# On_Axis_Encoder.net
KiCad netlist of a schematic drawn in EAGLE
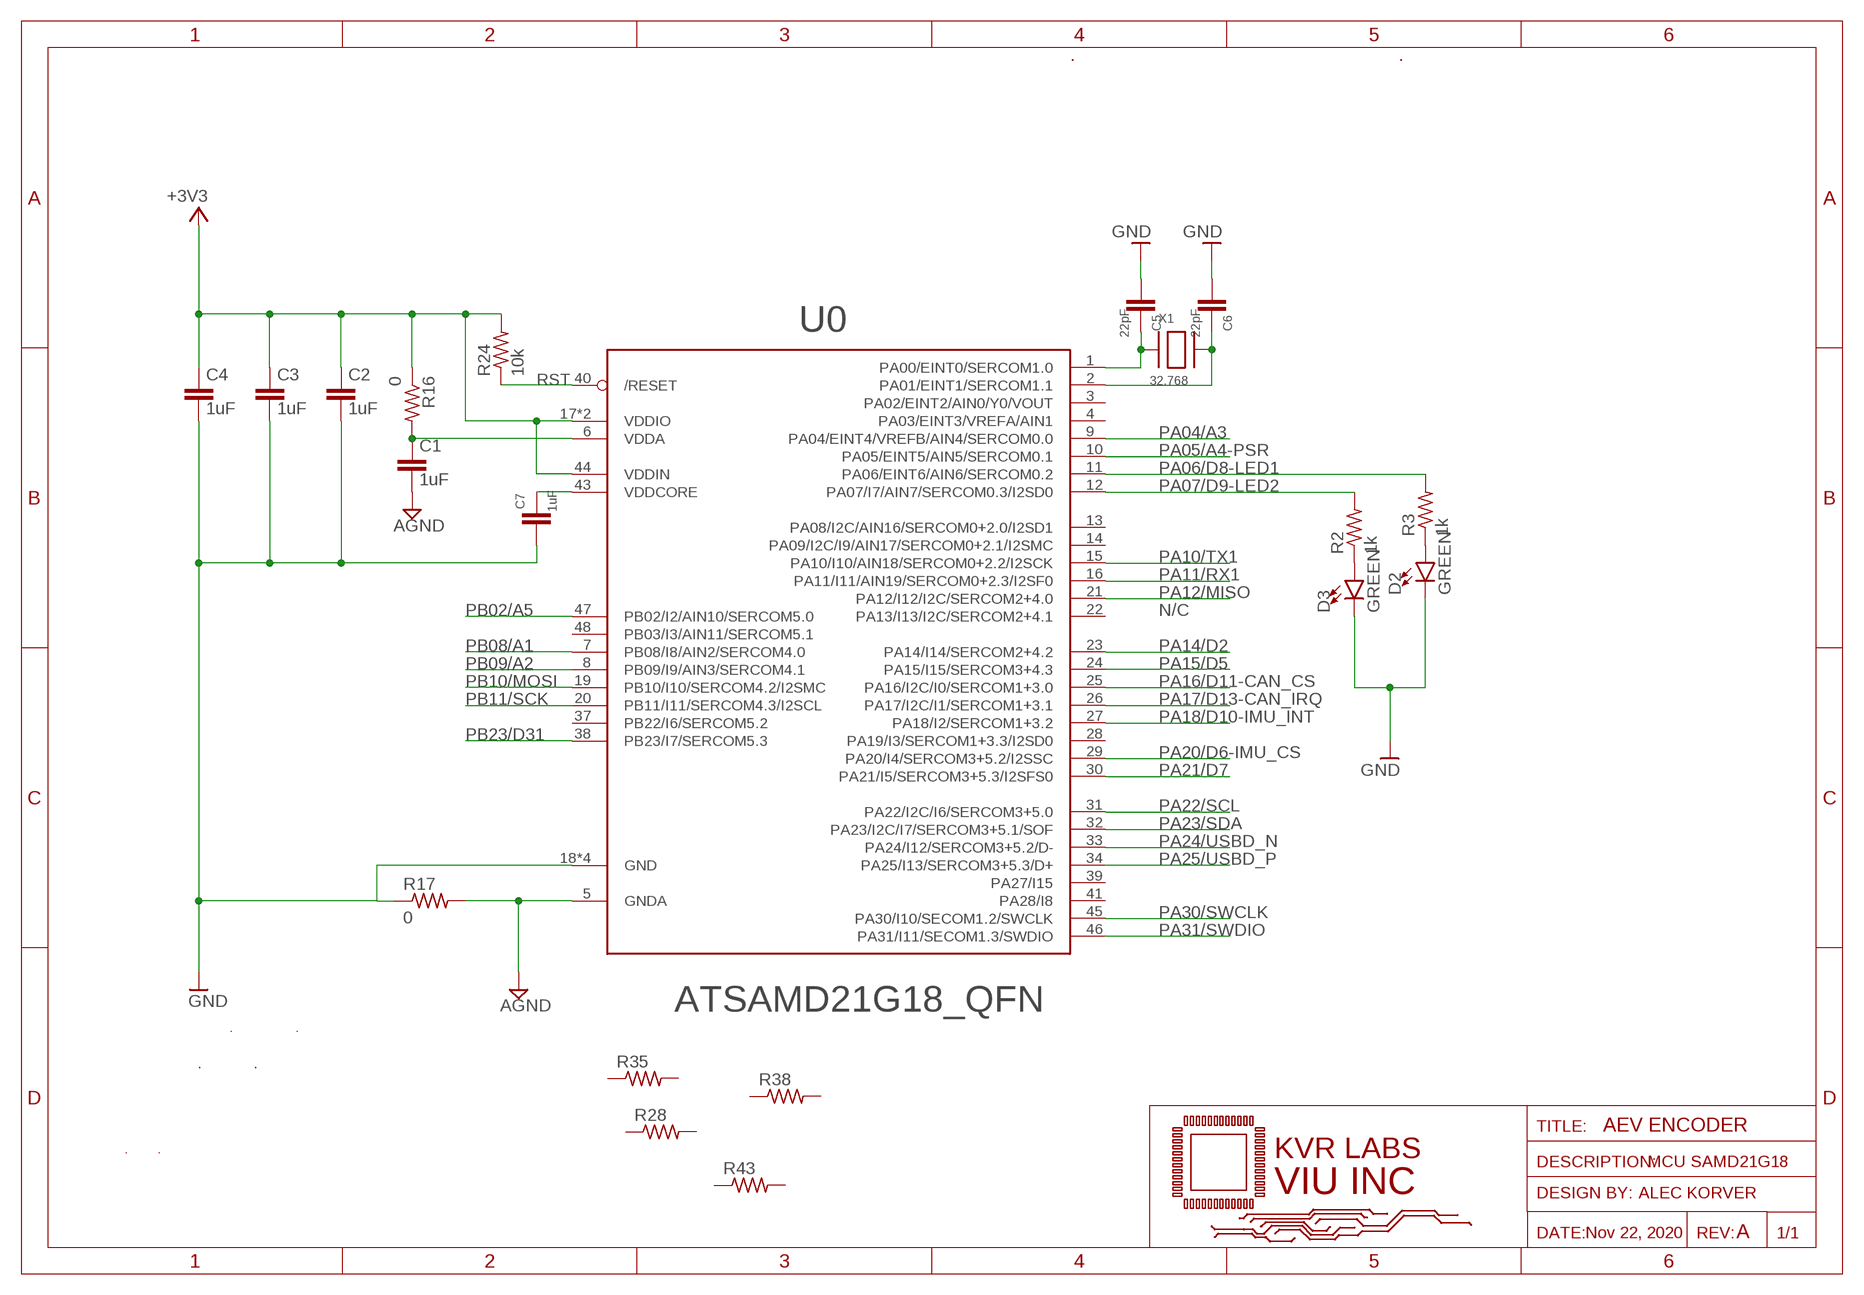
[diagram p0: schematic, sheet 1]
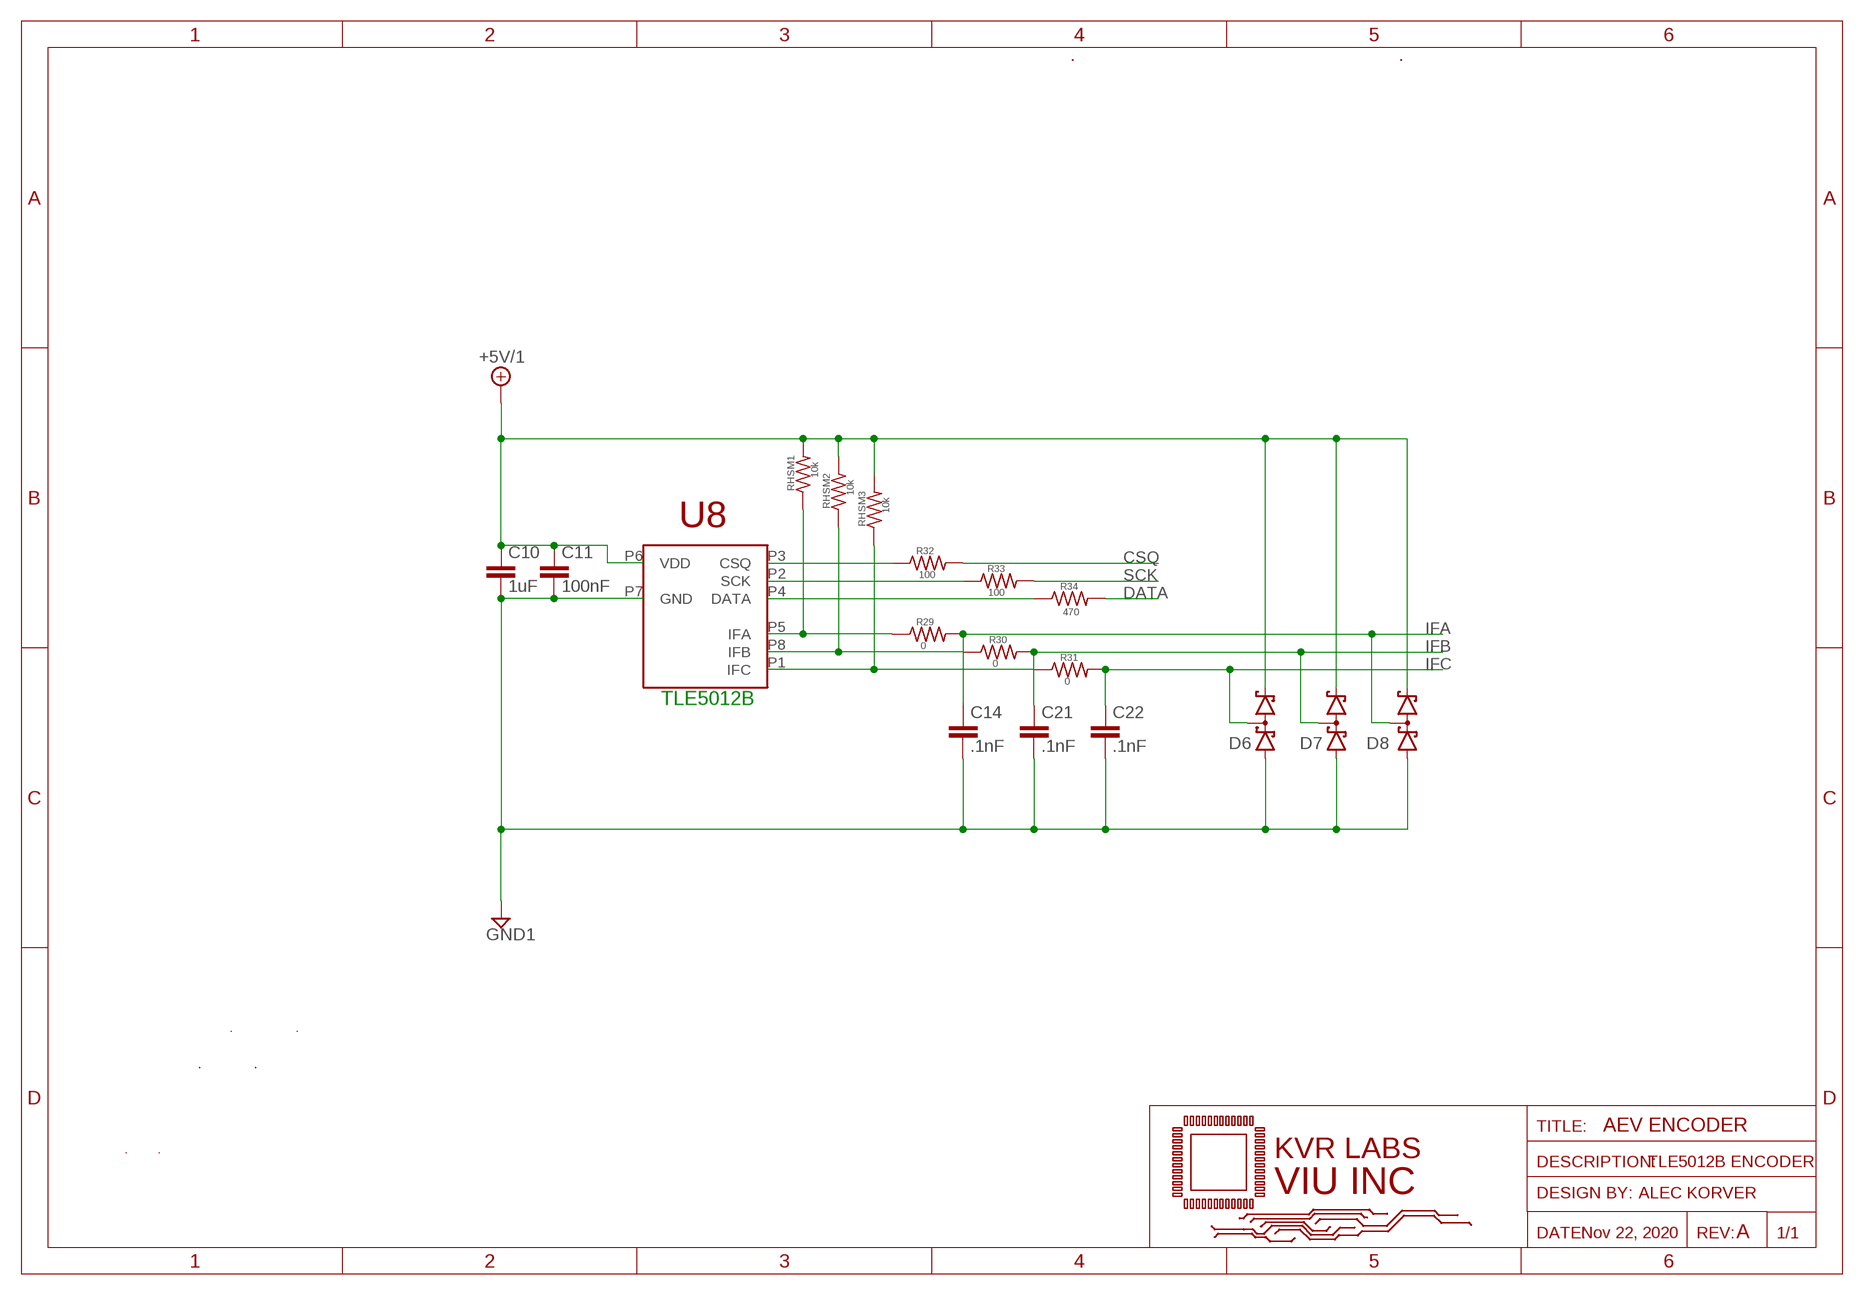
[diagram p1: schematic, sheet 2]
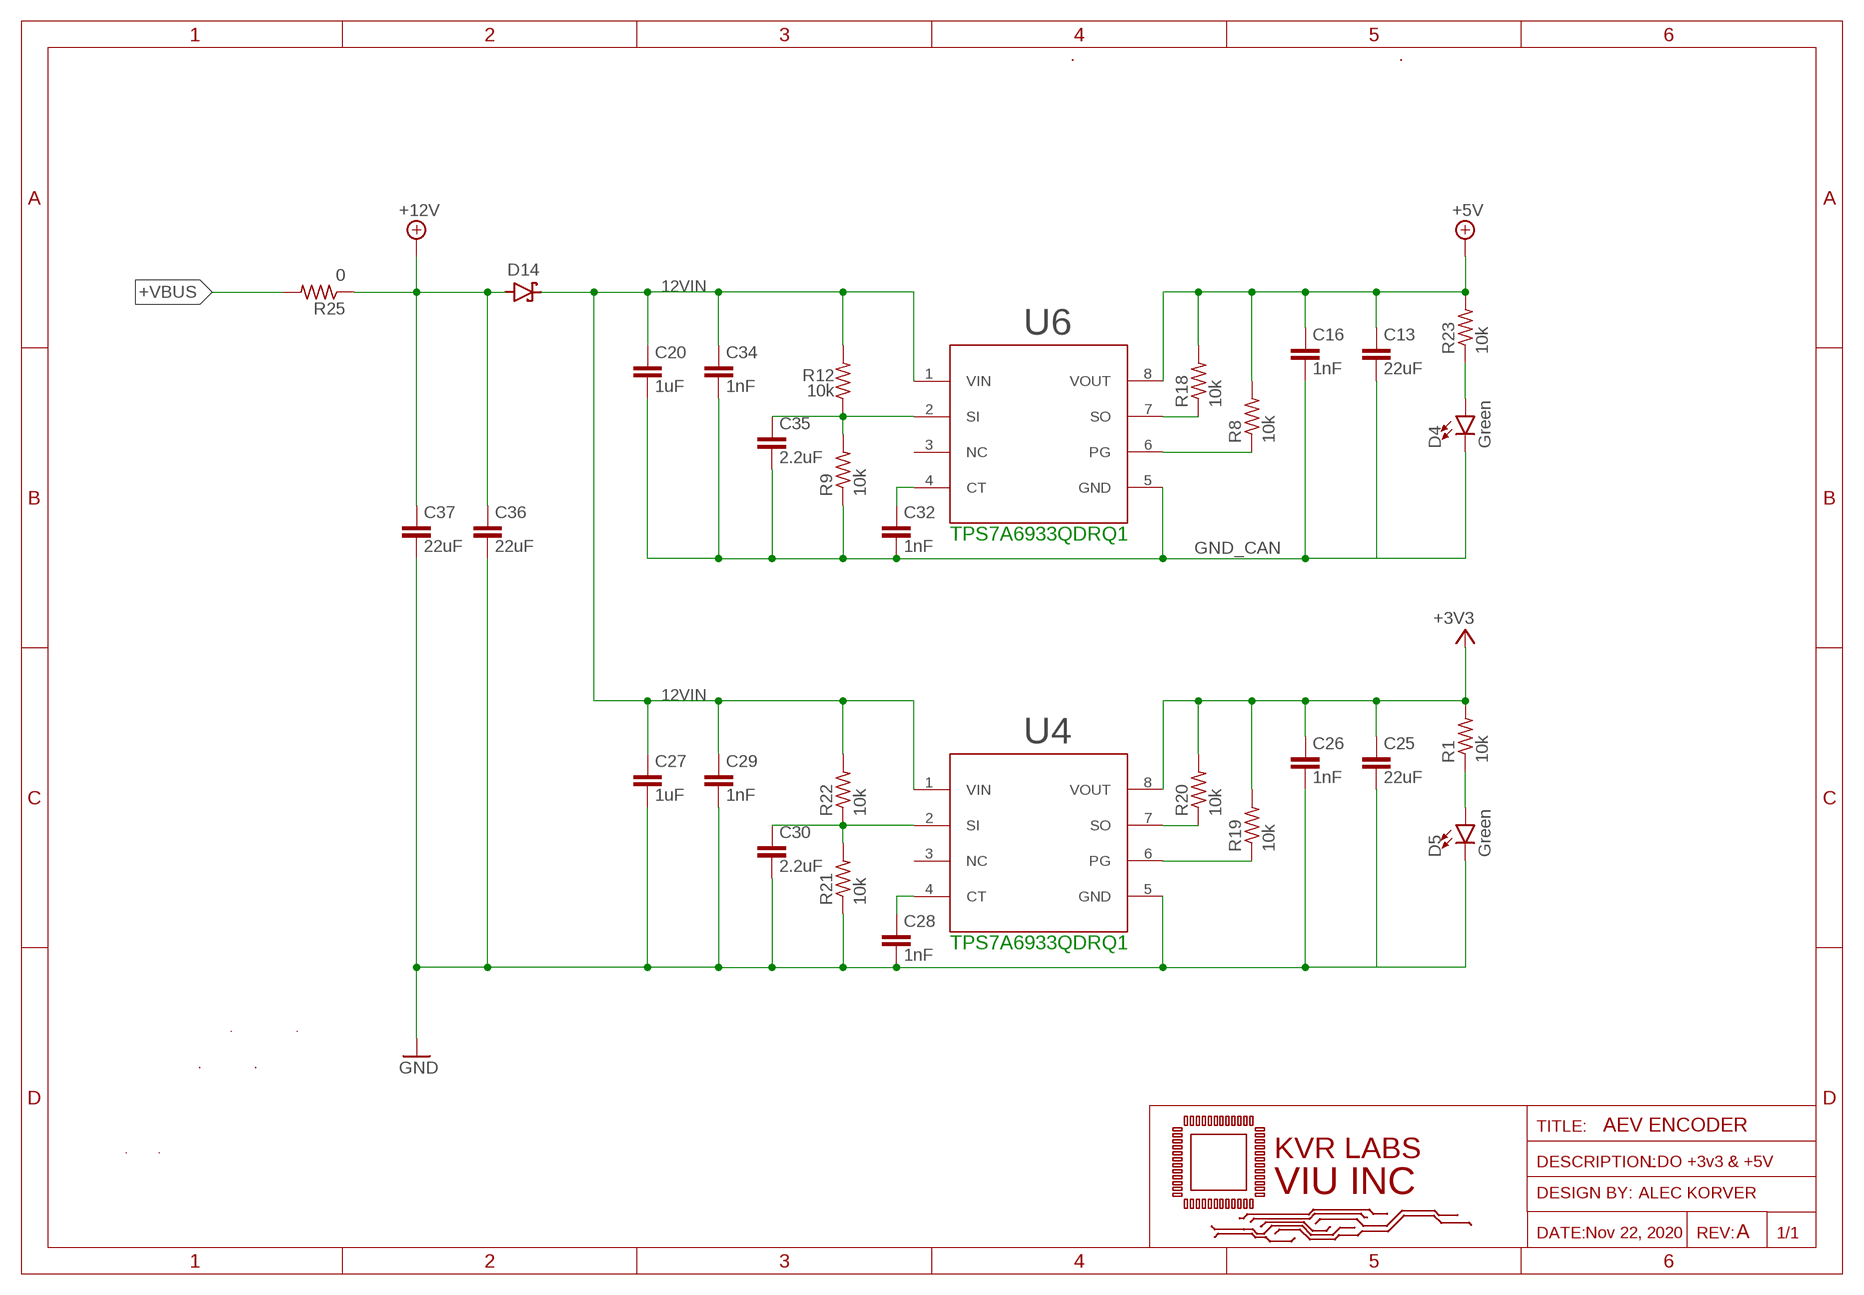
[diagram p2: schematic, sheet 3]
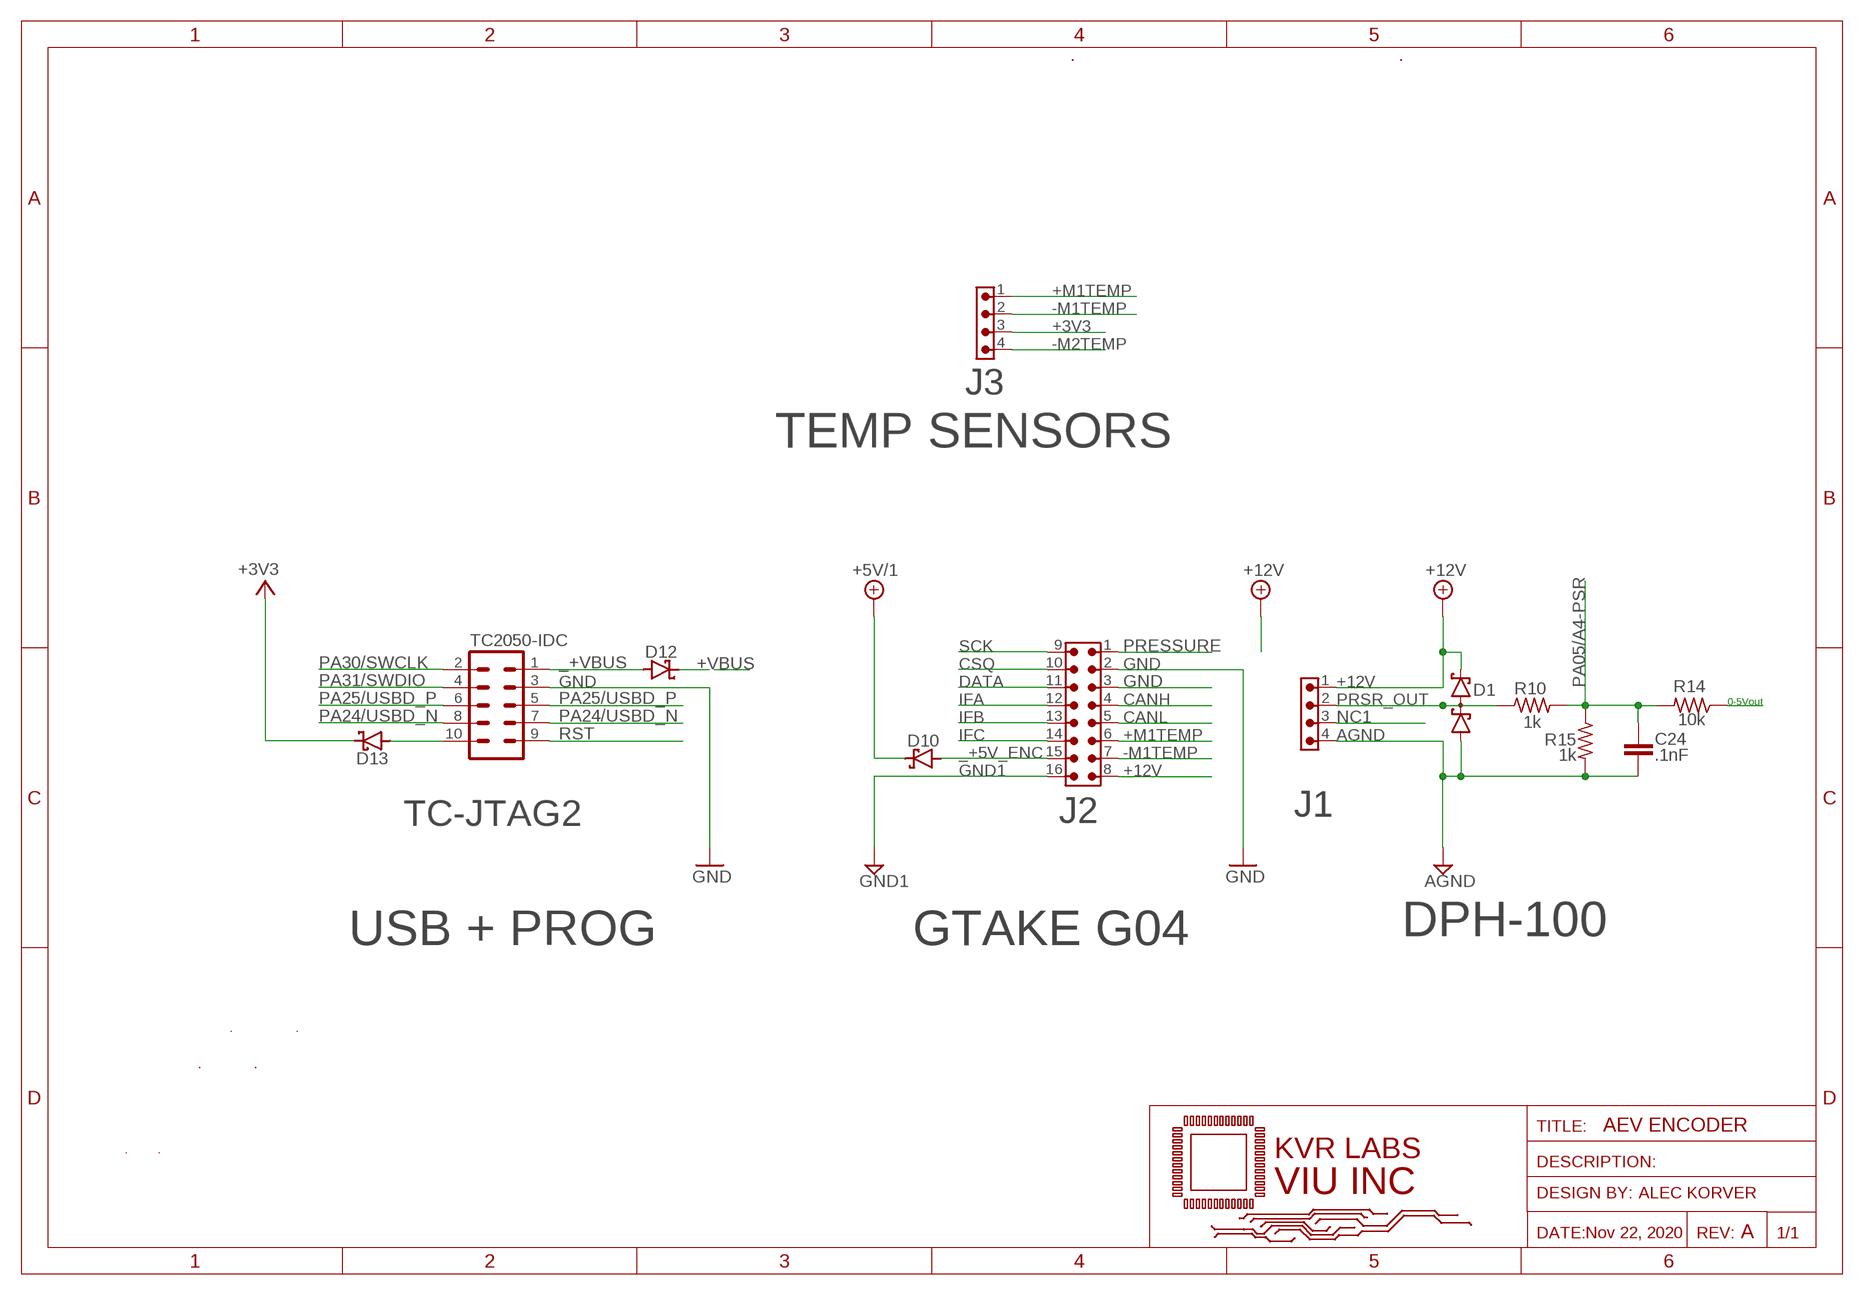
[diagram p3: schematic, sheet 4]
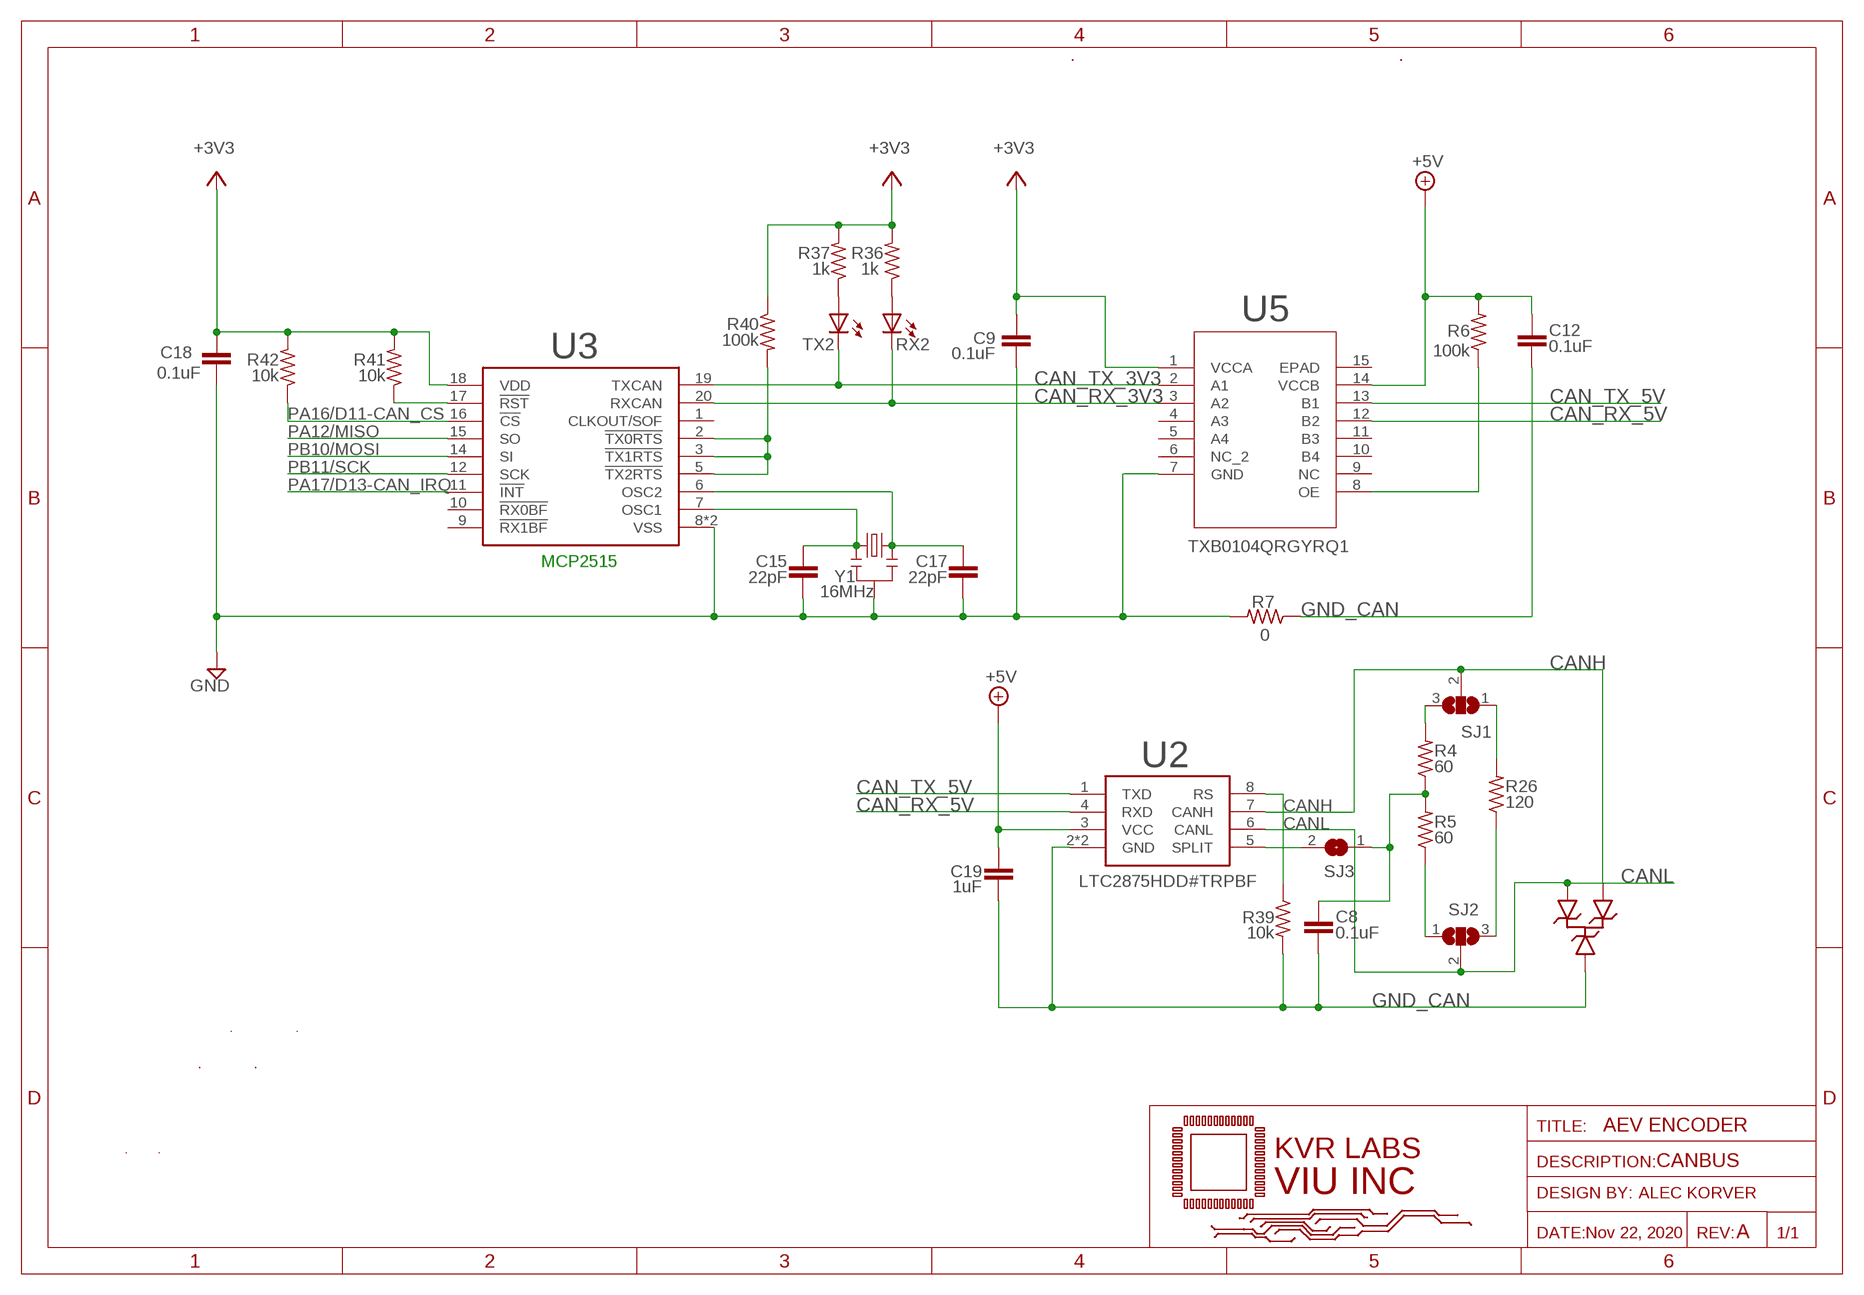
[diagram p4: schematic, sheet 5]
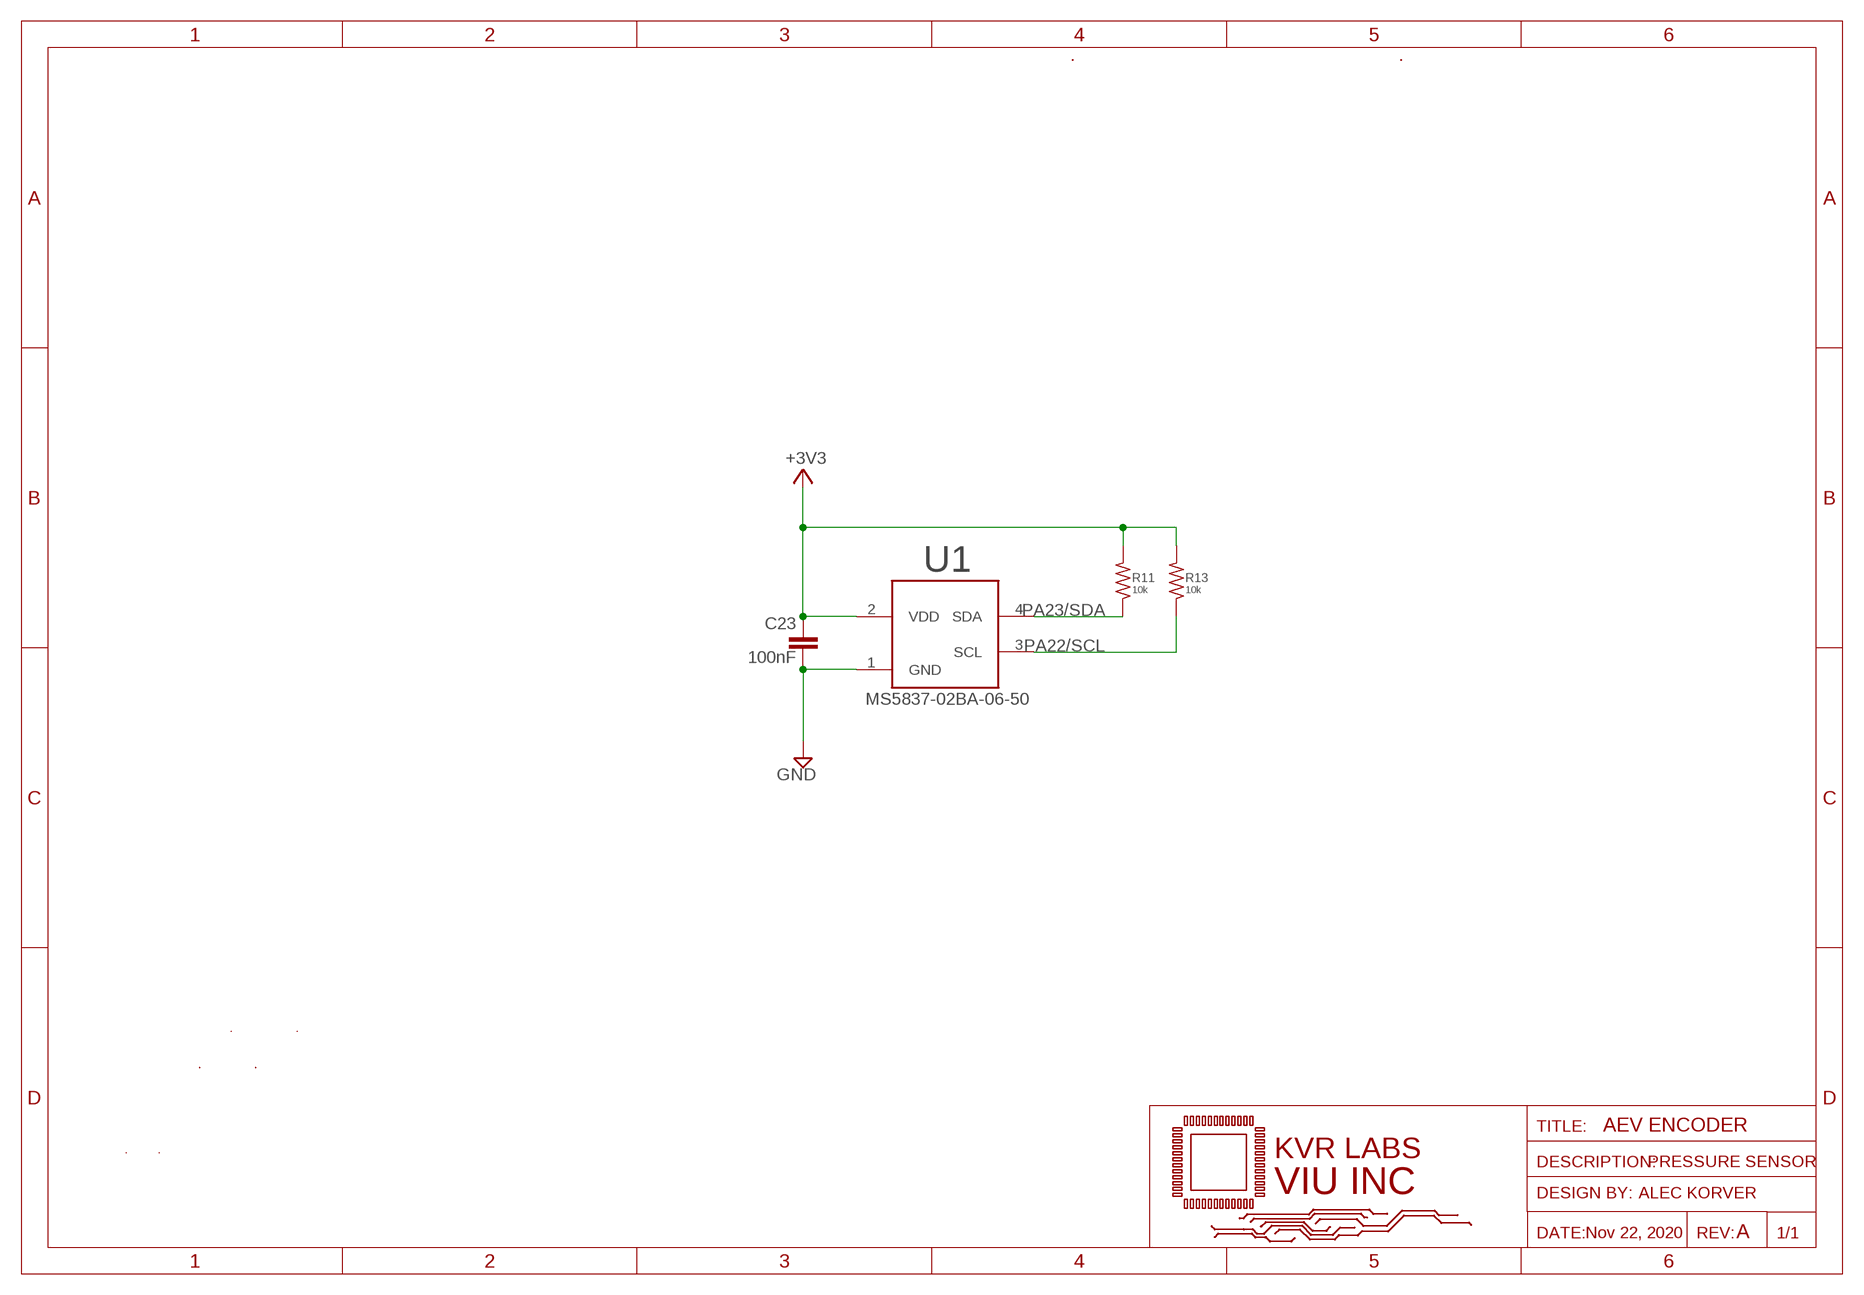
[diagram p5: schematic, sheet 6]
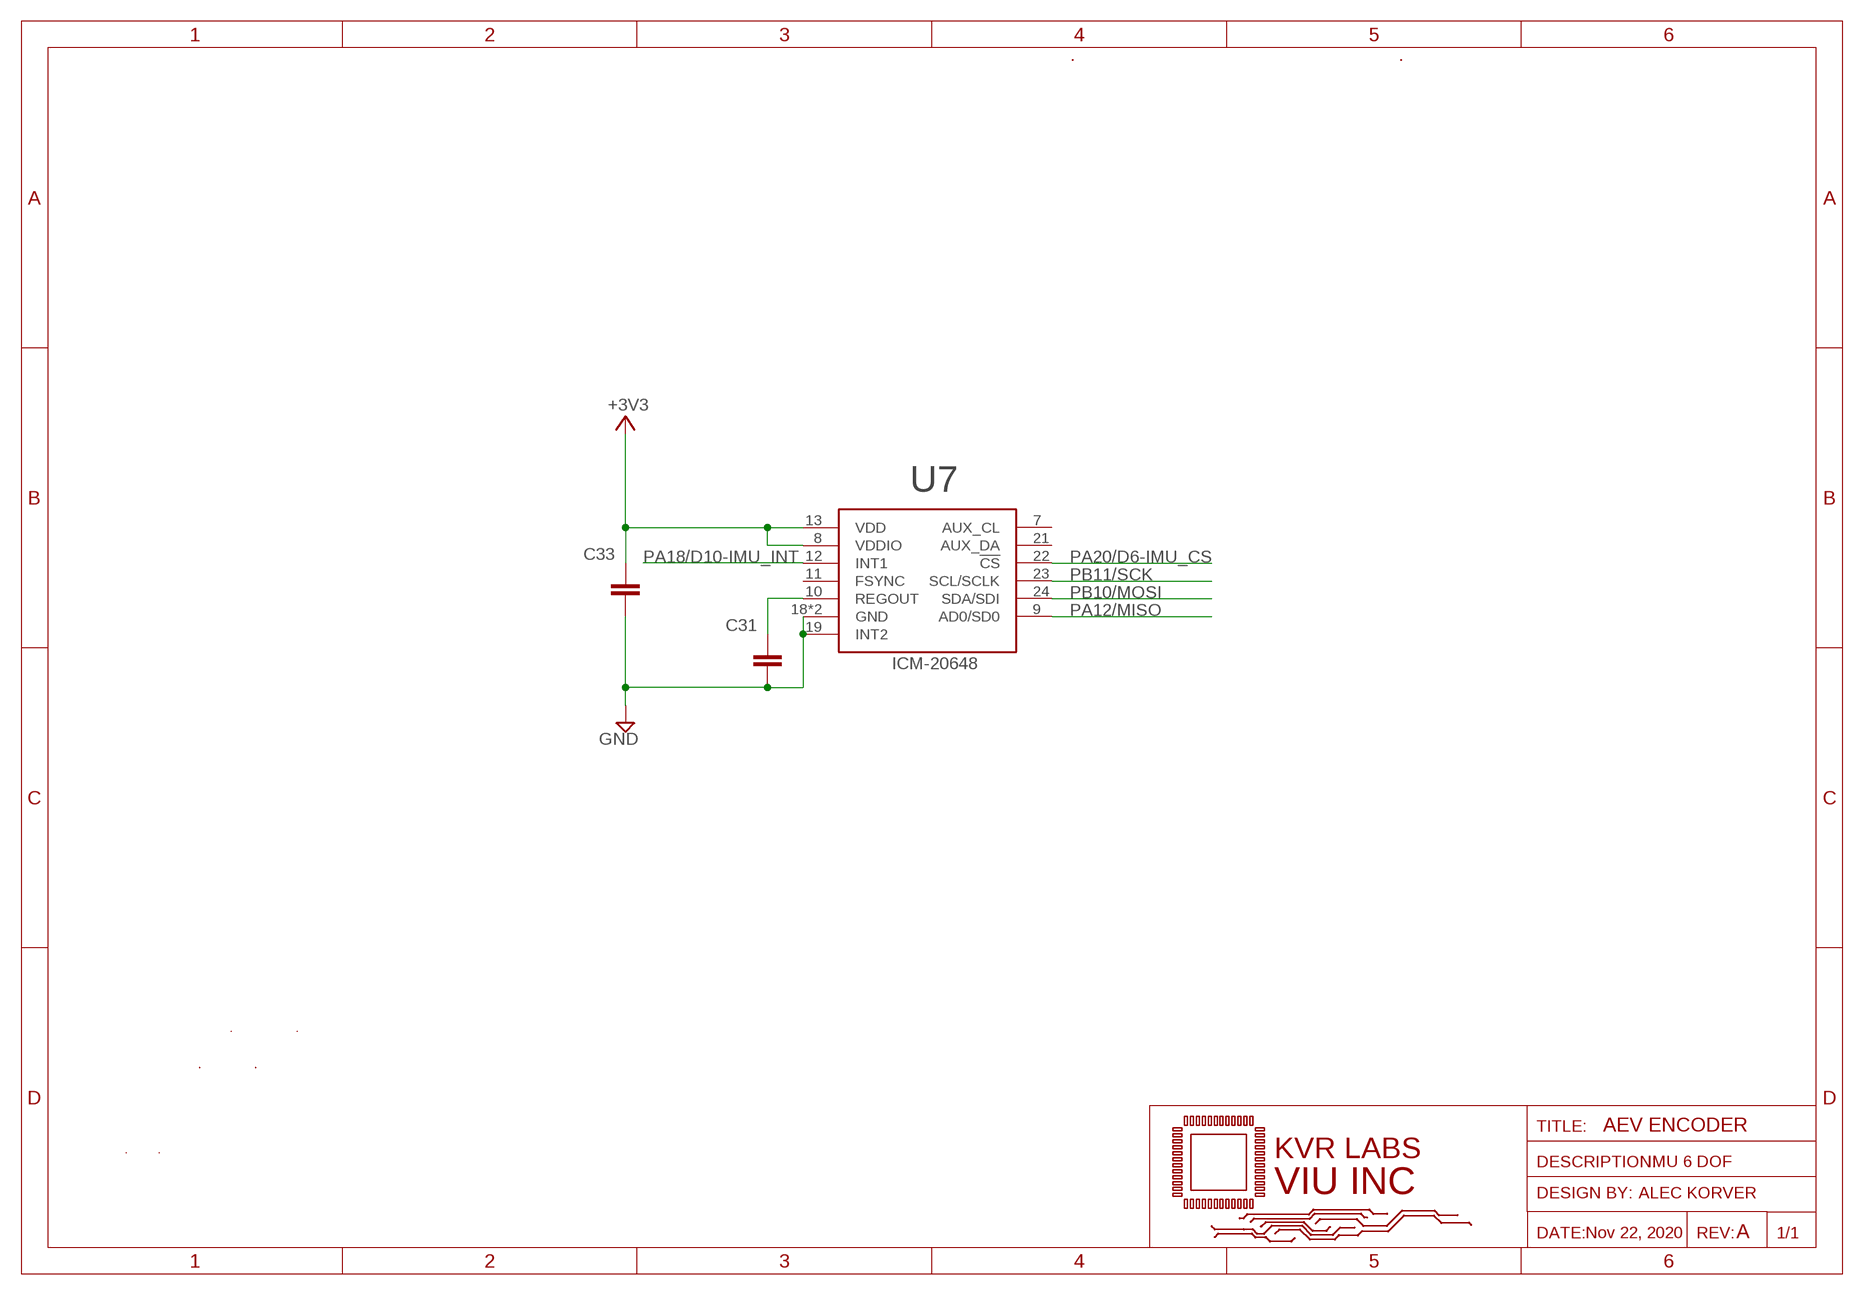
[diagram p6: schematic, sheet 7]
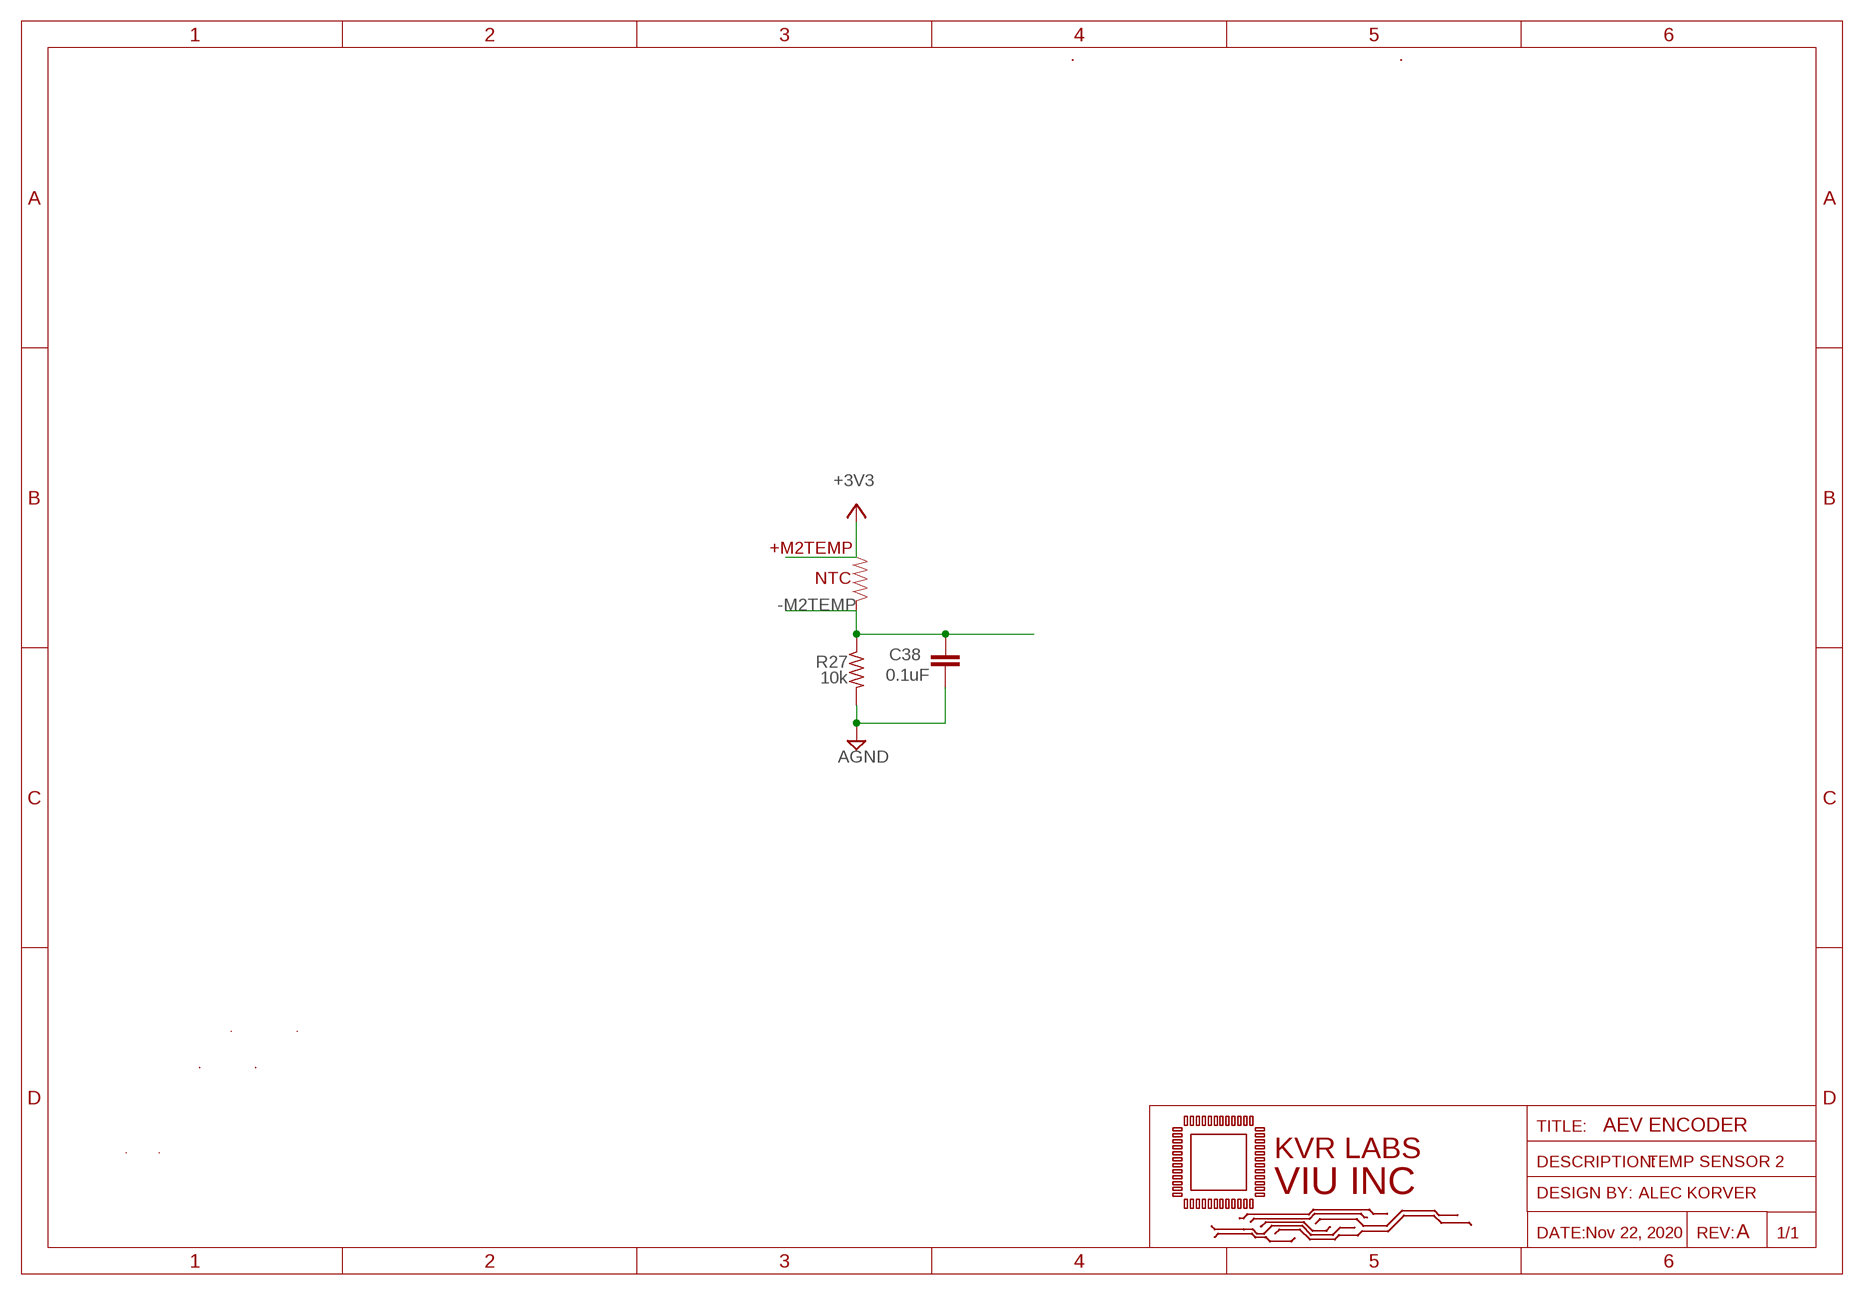
[diagram p7: schematic, sheet 8]

(export (version "E")
  (design (tool "Eeschema 10.0.6"))
  (components
    (comp (ref "C24")
      (value ".1nF")
      (footprint "eagle-import:C0805")
      (libsource (lib "eagle-import") (part "rcl_334_C-EUC0805"))
    )
    (comp (ref "D1")
      (value "BAS70-04")
      (footprint "eagle-import:SOT23")
      (libsource (lib "eagle-import") (part "BAS70-04"))
    )
    (comp (ref "D10")
      (value "MBR0520LT1G")
      (footprint "eagle-import:SODFL3718X115")
      (fields (field (name "MANUFACTURER") "ON Semiconductor"))
      (libsource (lib "eagle-import") (part "SCHOTTKY_DO-219MBR0520LT1G"))
    )
    (comp (ref "D12")
      (value "MBR0520LT1G")
      (footprint "eagle-import:SODFL3718X115")
      (fields (field (name "MANUFACTURER") "ON Semiconductor"))
      (libsource (lib "eagle-import") (part "SCHOTTKY_DO-219MBR0520LT1G"))
    )
    (comp (ref "D13")
      (value "MBR0520LT1G")
      (footprint "eagle-import:SODFL3718X115")
      (fields (field (name "MANUFACTURER") "ON Semiconductor"))
      (libsource (lib "eagle-import") (part "SCHOTTKY_DO-219MBR0520LT1G"))
    )
    (comp (ref "J1")
      (value "6620XX11122_66200411122")
      (footprint "eagle-import:66200411122")
      (libsource (lib "eagle-import") (part "6620XX11122_66200411122"))
    )
    (comp (ref "J2")
      (value "6620XX21122_66201621122")
      (footprint "eagle-import:66201621122")
      (libsource (lib "eagle-import") (part "6620XX21122_66201621122"))
    )
    (comp (ref "J3")
      (value "6620XX11122_66200411122")
      (footprint "eagle-import:66200411122")
      (libsource (lib "eagle-import") (part "6620XX11122_66200411122"))
    )
    (comp (ref "R10")
      (value "1k")
      (footprint "eagle-import:R0805")
      (libsource (lib "eagle-import") (part "rcl_23965951_R-US_R0805"))
    )
    (comp (ref "R14")
      (value "10k")
      (footprint "eagle-import:R0805")
      (libsource (lib "eagle-import") (part "rcl_23965951_R-US_R0805"))
    )
    (comp (ref "R15")
      (value "1k")
      (footprint "eagle-import:R0805")
      (libsource (lib "eagle-import") (part "rcl_23965951_R-US_R0805"))
    )
    (comp (ref "TC-JTAG2")
      (value "TC2050-IDC")
      (footprint "eagle-import:TC2050-IDC")
      (libsource (lib "eagle-import") (part "TC2050-IDC"))
    )
    (comp (ref "C23")
      (value "100nF")
      (footprint "eagle-import:C0603")
      (libsource (lib "eagle-import") (part "C-EUC0603"))
    )
    (comp (ref "R11")
      (value "10k")
      (footprint "eagle-import:R0603")
      (libsource (lib "eagle-import") (part "R-US_R0603"))
    )
    (comp (ref "R13")
      (value "10k")
      (footprint "eagle-import:R0603")
      (libsource (lib "eagle-import") (part "R-US_R0603"))
    )
    (comp (ref "U1")
      (value "MS5837-02BA-06-50")
      (footprint "eagle-import:DFN330X330X275-4N")
      (libsource (lib "eagle-import") (part "MS5837-02BA-06-50"))
    )
    (comp (ref "C8")
      (value "0.1uF")
      (footprint "eagle-import:C0805")
      (libsource (lib "eagle-import") (part "rcl_334_C-EUC0805"))
    )
    (comp (ref "C9")
      (value "0.1uF")
      (footprint "eagle-import:C0805")
      (libsource (lib "eagle-import") (part "rcl_334_C-EUC0805"))
    )
    (comp (ref "C12")
      (value "0.1uF")
      (footprint "eagle-import:C0805")
      (libsource (lib "eagle-import") (part "rcl_334_C-EUC0805"))
    )
    (comp (ref "C15")
      (value "22pF")
      (footprint "eagle-import:C0805")
      (libsource (lib "eagle-import") (part "rcl_334_C-EUC0805"))
    )
    (comp (ref "C17")
      (value "22pF")
      (footprint "eagle-import:C0805")
      (libsource (lib "eagle-import") (part "rcl_334_C-EUC0805"))
    )
    (comp (ref "C18")
      (value "0.1uF")
      (footprint "eagle-import:C0805")
      (libsource (lib "eagle-import") (part "rcl_334_C-EUC0805"))
    )
    (comp (ref "C19")
      (value "1uF")
      (footprint "eagle-import:C0805")
      (libsource (lib "eagle-import") (part "rcl_334_C-EUC0805"))
    )
    (comp (ref "R4")
      (value "60")
      (footprint "eagle-import:R0805")
      (libsource (lib "eagle-import") (part "rcl_23965951_R-US_R0805"))
    )
    (comp (ref "R5")
      (value "60")
      (footprint "eagle-import:R0805")
      (libsource (lib "eagle-import") (part "rcl_23965951_R-US_R0805"))
    )
    (comp (ref "R6")
      (value "100k")
      (footprint "eagle-import:R0805")
      (libsource (lib "eagle-import") (part "rcl_23965951_R-US_R0805"))
    )
    (comp (ref "R7")
      (value "0")
      (footprint "eagle-import:R0805")
      (libsource (lib "eagle-import") (part "rcl_23965951_R-US_R0805"))
    )
    (comp (ref "R26")
      (value "120")
      (footprint "eagle-import:R0805")
      (libsource (lib "eagle-import") (part "rcl_23965951_R-US_R0805"))
    )
    (comp (ref "R36")
      (value "1k")
      (footprint "eagle-import:R0805")
      (libsource (lib "eagle-import") (part "rcl_23965951_R-US_R0805"))
    )
    (comp (ref "R37")
      (value "1k")
      (footprint "eagle-import:R0805")
      (libsource (lib "eagle-import") (part "rcl_23965951_R-US_R0805"))
    )
    (comp (ref "R39")
      (value "10k")
      (footprint "eagle-import:R0805")
      (fields (field (name "SPICEPREFIX") "R"))
      (libsource (lib "eagle-import") (part "rcl_23965951_R-US_R0805"))
    )
    (comp (ref "R40")
      (value "100k")
      (footprint "eagle-import:R0805")
      (libsource (lib "eagle-import") (part "rcl_23965951_R-US_R0805"))
    )
    (comp (ref "R41")
      (value "10k")
      (footprint "eagle-import:R0805")
      (libsource (lib "eagle-import") (part "rcl_23965951_R-US_R0805"))
    )
    (comp (ref "R42")
      (value "10k")
      (footprint "eagle-import:R0805")
      (libsource (lib "eagle-import") (part "rcl_23965951_R-US_R0805"))
    )
    (comp (ref "RX2")
      (value "LEDCHIPLED_0805")
      (footprint "eagle-import:CHIPLED_0805")
      (libsource (lib "eagle-import") (part "LEDCHIPLED_0805"))
    )
    (comp (ref "SJ1")
      (value "SJ2W")
      (footprint "eagle-import:SJ_2")
      (libsource (lib "eagle-import") (part "SJ2W"))
    )
    (comp (ref "SJ2")
      (value "SJ2W")
      (footprint "eagle-import:SJ_2")
      (libsource (lib "eagle-import") (part "SJ2W"))
    )
    (comp (ref "SJ3") (value "SJ") (footprint "eagle-import:SJ") (libsource (lib "eagle-import") (part "SJ")))
    (comp (ref "TX2")
      (value "LEDCHIPLED_0805")
      (footprint "eagle-import:CHIPLED_0805")
      (libsource (lib "eagle-import") (part "LEDCHIPLED_0805"))
    )
    (comp (ref "U$2")
      (value "μCLAMP2492SQ")
      (footprint "eagle-import:SOT-23_3L_ONS")
      (libsource (lib "eagle-import") (part "μCLAMP2492SQ"))
    )
    (comp (ref "U2")
      (value "LTC2875HDD#TRPBF")
      (footprint "eagle-import:SON50P300X300X80-9T165X238N")
      (libsource (lib "eagle-import") (part "LTC2875-8-DFN"))
    )
    (comp (ref "U3")
      (value "MCP2515-E/ML")
      (footprint "eagle-import:QFN50P400X400X100-21T270N")
      (libsource (lib "eagle-import") (part "MCP2515QFN-20"))
    )
    (comp (ref "U5")
      (value "TXB0104QRGYRQ1")
      (footprint "eagle-import:RGY14_2P05X2P05")
      (fields
        (field (name "GENERIC_PART_NUMBER") "TXB0104-Q1")
        (field (name "MANUFACTURER") "Texas Instruments")
      )
      (libsource (lib "eagle-import") (part "TXB0104QRGYRQ1"))
    )
    (comp (ref "Y1")
      (value "16MHz")
      (footprint "eagle-import:RESONATOR-SMD")
      (libsource (lib "eagle-import") (part "RESONATORSMD"))
    )
    (comp (ref "C1")
      (value "1uF")
      (footprint "eagle-import:C0805")
      (libsource (lib "eagle-import") (part "rcl_334_C-EUC0805"))
    )
    (comp (ref "C2")
      (value "1uF")
      (footprint "eagle-import:C0805")
      (libsource (lib "eagle-import") (part "rcl_334_C-EUC0805"))
    )
    (comp (ref "C3")
      (value "1uF")
      (footprint "eagle-import:C0805")
      (libsource (lib "eagle-import") (part "rcl_334_C-EUC0805"))
    )
    (comp (ref "C4")
      (value "1uF")
      (footprint "eagle-import:C0805")
      (libsource (lib "eagle-import") (part "rcl_334_C-EUC0805"))
    )
    (comp (ref "C5")
      (value "22pF")
      (footprint "eagle-import:C0805")
      (libsource (lib "eagle-import") (part "rcl_334_C-EUC0805"))
    )
    (comp (ref "C6")
      (value "22pF")
      (footprint "eagle-import:C0805")
      (libsource (lib "eagle-import") (part "rcl_334_C-EUC0805"))
    )
    (comp (ref "C7")
      (value "1uF")
      (footprint "eagle-import:C0805")
      (libsource (lib "eagle-import") (part "rcl_334_C-EUC0805"))
    )
    (comp (ref "D2")
      (value "GREEN")
      (footprint "eagle-import:LED-0603")
      (libsource (lib "eagle-import") (part "LED-RED0603"))
    )
    (comp (ref "D3")
      (value "GREEN")
      (footprint "eagle-import:LED-0603")
      (libsource (lib "eagle-import") (part "LED-RED0603"))
    )
    (comp (ref "R2")
      (value "1k")
      (footprint "eagle-import:R0603")
      (libsource (lib "eagle-import") (part "rcl_334_R-US_R0603"))
    )
    (comp (ref "R3")
      (value "1k")
      (footprint "eagle-import:R0603")
      (libsource (lib "eagle-import") (part "rcl_334_R-US_R0603"))
    )
    (comp (ref "R16")
      (value "0")
      (footprint "eagle-import:R0805")
      (libsource (lib "eagle-import") (part "rcl_23965951_R-US_R0805"))
    )
    (comp (ref "R17")
      (value "0")
      (footprint "eagle-import:R0805")
      (libsource (lib "eagle-import") (part "rcl_23965951_R-US_R0805"))
    )
    (comp (ref "R24")
      (value "10k")
      (footprint "eagle-import:R0805")
      (libsource (lib "eagle-import") (part "rcl_23965951_R-US_R0805"))
    )
    (comp (ref "R28")
      (value "R-US_R0603")
      (footprint "eagle-import:R0603")
      (libsource (lib "eagle-import") (part "rcl_334_R-US_R0603"))
    )
    (comp (ref "R35")
      (value "R-US_R0402")
      (footprint "eagle-import:R0402")
      (libsource (lib "eagle-import") (part "rcl_334_R-US_R0402"))
    )
    (comp (ref "R38")
      (value "R-US_R0201")
      (footprint "eagle-import:R0201")
      (libsource (lib "eagle-import") (part "rcl_334_R-US_R0201"))
    )
    (comp (ref "R43")
      (value "R-US_R0805")
      (footprint "eagle-import:R0805")
      (libsource (lib "eagle-import") (part "rcl_334_R-US_R0805"))
    )
    (comp (ref "U0")
      (value "ATSAMD21G18_QFN")
      (footprint "eagle-import:MICROBUILDER_TQFN48_7MM")
      (libsource (lib "eagle-import") (part "ATSAMD21J_QFN"))
    )
    (comp (ref "X1")
      (value "32.768")
      (footprint "eagle-import:XTAL3215")
      (libsource (lib "eagle-import") (part "XTAL-3.2X1.5"))
    )
    (comp (ref "C31")
      (value "0.1uF")
      (footprint "eagle-import:0603")
      (libsource (lib "eagle-import") (part "C0603"))
    )
    (comp (ref "C33")
      (value "0.1uF")
      (footprint "eagle-import:0603")
      (libsource (lib "eagle-import") (part "C0603"))
    )
    (comp (ref "U7")
      (value "ICM-20648")
      (footprint "eagle-import:ICM-20648")
      (libsource (lib "eagle-import") (part "ICM-20648"))
    )
    (comp (ref "C13")
      (value "22uF")
      (footprint "eagle-import:C0805")
      (libsource (lib "eagle-import") (part "rcl_334_C-EUC0805"))
    )
    (comp (ref "C16")
      (value "1nF")
      (footprint "eagle-import:C0805")
      (libsource (lib "eagle-import") (part "rcl_334_C-EUC0805"))
    )
    (comp (ref "C20")
      (value "1uF")
      (footprint "eagle-import:C0805")
      (libsource (lib "eagle-import") (part "rcl_334_C-EUC0805"))
    )
    (comp (ref "C25")
      (value "22uF")
      (footprint "eagle-import:C0805")
      (libsource (lib "eagle-import") (part "rcl_334_C-EUC0805"))
    )
    (comp (ref "C26")
      (value "1nF")
      (footprint "eagle-import:C0805")
      (libsource (lib "eagle-import") (part "rcl_334_C-EUC0805"))
    )
    (comp (ref "C27")
      (value "1uF")
      (footprint "eagle-import:C0805")
      (libsource (lib "eagle-import") (part "rcl_334_C-EUC0805"))
    )
    (comp (ref "C28")
      (value "1nF")
      (footprint "eagle-import:C0805")
      (libsource (lib "eagle-import") (part "rcl_334_C-EUC0805"))
    )
    (comp (ref "C29")
      (value "1nF")
      (footprint "eagle-import:C0805")
      (libsource (lib "eagle-import") (part "rcl_334_C-EUC0805"))
    )
    (comp (ref "C30")
      (value "2.2uF")
      (footprint "eagle-import:C0805")
      (libsource (lib "eagle-import") (part "rcl_334_C-EUC0805"))
    )
    (comp (ref "C32")
      (value "1nF")
      (footprint "eagle-import:C0805")
      (libsource (lib "eagle-import") (part "rcl_334_C-EUC0805"))
    )
    (comp (ref "C34")
      (value "1nF")
      (footprint "eagle-import:C0805")
      (libsource (lib "eagle-import") (part "rcl_334_C-EUC0805"))
    )
    (comp (ref "C35")
      (value "2.2uF")
      (footprint "eagle-import:C0805")
      (libsource (lib "eagle-import") (part "rcl_334_C-EUC0805"))
    )
    (comp (ref "C36")
      (value "22uF")
      (footprint "eagle-import:C1206")
      (libsource (lib "eagle-import") (part "rcl_334_C-EUC1206"))
    )
    (comp (ref "C37")
      (value "22uF")
      (footprint "eagle-import:C1206")
      (libsource (lib "eagle-import") (part "rcl_334_C-EUC1206"))
    )
    (comp (ref "D4")
      (value "Green")
      (footprint "eagle-import:LED-1206-BOTTOM")
      (libsource (lib "eagle-import") (part "LED-GREEN1206-BOTTOM"))
    )
    (comp (ref "D5")
      (value "Green")
      (footprint "eagle-import:LED-1206-BOTTOM")
      (libsource (lib "eagle-import") (part "LED-GREEN1206-BOTTOM"))
    )
    (comp (ref "D14")
      (value "MBR0520LT1G")
      (footprint "eagle-import:SODFL3718X115")
      (fields (field (name "MANUFACTURER") "ON Semiconductor"))
      (libsource (lib "eagle-import") (part "SCHOTTKY_DO-219MBR0520LT1G"))
    )
    (comp (ref "R1")
      (value "10k")
      (footprint "eagle-import:R0805")
      (libsource (lib "eagle-import") (part "rcl_23965951_R-US_R0805"))
    )
    (comp (ref "R8")
      (value "10k")
      (footprint "eagle-import:R0805")
      (libsource (lib "eagle-import") (part "rcl_23965951_R-US_R0805"))
    )
    (comp (ref "R9")
      (value "10k")
      (footprint "eagle-import:R0805")
      (libsource (lib "eagle-import") (part "rcl_23965951_R-US_R0805"))
    )
    (comp (ref "R12")
      (value "10k")
      (footprint "eagle-import:R0805")
      (libsource (lib "eagle-import") (part "rcl_23965951_R-US_R0805"))
    )
    (comp (ref "R18")
      (value "10k")
      (footprint "eagle-import:R0805")
      (libsource (lib "eagle-import") (part "rcl_23965951_R-US_R0805"))
    )
    (comp (ref "R19")
      (value "10k")
      (footprint "eagle-import:R0805")
      (libsource (lib "eagle-import") (part "rcl_23965951_R-US_R0805"))
    )
    (comp (ref "R20")
      (value "10k")
      (footprint "eagle-import:R0805")
      (libsource (lib "eagle-import") (part "rcl_23965951_R-US_R0805"))
    )
    (comp (ref "R21")
      (value "10k")
      (footprint "eagle-import:R0805")
      (libsource (lib "eagle-import") (part "rcl_23965951_R-US_R0805"))
    )
    (comp (ref "R22")
      (value "10k")
      (footprint "eagle-import:R0805")
      (libsource (lib "eagle-import") (part "rcl_23965951_R-US_R0805"))
    )
    (comp (ref "R23")
      (value "10k")
      (footprint "eagle-import:R0805")
      (libsource (lib "eagle-import") (part "rcl_23965951_R-US_R0805"))
    )
    (comp (ref "R25")
      (value "0")
      (footprint "eagle-import:R0805")
      (libsource (lib "eagle-import") (part "rcl_23965951_R-US_R0805"))
    )
    (comp (ref "U4")
      (value "Value")
      (footprint "eagle-import:D0008A_N")
      (fields (field (name "MANUFACTURER") "Texas Instruments") (field (name "PARTNUMBER") "TPS7A6933QDRQ1"))
      (libsource (lib "eagle-import") (part "TPS7A6933QDRQ1"))
    )
    (comp (ref "U6")
      (value "Value")
      (footprint "eagle-import:D0008A_N")
      (fields (field (name "MANUFACTURER") "Texas Instruments") (field (name "PARTNUMBER") "TPS7A6933QDRQ1"))
      (libsource (lib "eagle-import") (part "TPS7A6933QDRQ1"))
    )
    (comp (ref "C38")
      (value "0.1uF")
      (footprint "eagle-import:C0805")
      (libsource (lib "eagle-import") (part "rcl_334_C-EUC0805"))
    )
    (comp (ref "R27")
      (value "10k")
      (footprint "eagle-import:R0805")
      (libsource (lib "eagle-import") (part "rcl_23965951_R-US_R0805"))
    )
    (comp (ref "C10")
      (value "1uF")
      (footprint "eagle-import:C0805")
      (libsource (lib "eagle-import") (part "rcl_23965951_C-EUC0805"))
    )
    (comp (ref "C11")
      (value "100nF")
      (footprint "eagle-import:C0805")
      (libsource (lib "eagle-import") (part "rcl_23965951_C-EUC0805"))
    )
    (comp (ref "C14")
      (value ".1nF")
      (footprint "eagle-import:C0805")
      (libsource (lib "eagle-import") (part "rcl_23965951_C-EUC0805"))
    )
    (comp (ref "C21")
      (value ".1nF")
      (footprint "eagle-import:C0805")
      (libsource (lib "eagle-import") (part "rcl_23965951_C-EUC0805"))
    )
    (comp (ref "C22")
      (value ".1nF")
      (footprint "eagle-import:C0805")
      (libsource (lib "eagle-import") (part "rcl_23965951_C-EUC0805"))
    )
    (comp (ref "D6")
      (value "BAS70-04")
      (footprint "eagle-import:SOT23")
      (libsource (lib "eagle-import") (part "BAS70-04"))
    )
    (comp (ref "D7")
      (value "BAS70-04")
      (footprint "eagle-import:SOT23")
      (libsource (lib "eagle-import") (part "BAS70-04"))
    )
    (comp (ref "D8")
      (value "BAS70-04")
      (footprint "eagle-import:SOT23")
      (libsource (lib "eagle-import") (part "BAS70-04"))
    )
    (comp (ref "R29")
      (value "0")
      (footprint "eagle-import:R0805")
      (libsource (lib "eagle-import") (part "rcl_23965951_R-US_R0805"))
    )
    (comp (ref "R30")
      (value "0")
      (footprint "eagle-import:R0805")
      (libsource (lib "eagle-import") (part "rcl_23965951_R-US_R0805"))
    )
    (comp (ref "R31")
      (value "0")
      (footprint "eagle-import:R0805")
      (libsource (lib "eagle-import") (part "rcl_23965951_R-US_R0805"))
    )
    (comp (ref "R32")
      (value "100")
      (footprint "eagle-import:R0805")
      (libsource (lib "eagle-import") (part "rcl_23965951_R-US_R0805"))
    )
    (comp (ref "R33")
      (value "100")
      (footprint "eagle-import:R0805")
      (libsource (lib "eagle-import") (part "rcl_23965951_R-US_R0805"))
    )
    (comp (ref "R34")
      (value "470")
      (footprint "eagle-import:R0805")
      (libsource (lib "eagle-import") (part "rcl_23965951_R-US_R0805"))
    )
    (comp (ref "RHSM1")
      (value "10k")
      (footprint "eagle-import:R0805")
      (libsource (lib "eagle-import") (part "rcl_23965951_R-US_R0805"))
    )
    (comp (ref "RHSM2")
      (value "10k")
      (footprint "eagle-import:R0805")
      (libsource (lib "eagle-import") (part "rcl_23965951_R-US_R0805"))
    )
    (comp (ref "RHSM3")
      (value "10k")
      (footprint "eagle-import:R0805")
      (libsource (lib "eagle-import") (part "rcl_23965951_R-US_R0805"))
    )
    (comp (ref "U8")
      (value "TLE5012B")
      (footprint "eagle-import:PG-DSO-8")
      (libsource (lib "eagle-import") (part "TLE5012B"))
    )
  )
  (nets
    (net (code "1") (name "+3V3") (class "Default")
      (node (ref "C18") (pin "1") (pinfunction "1_1") (pintype "passive"))
      (node (ref "C2") (pin "1") (pinfunction "1_1") (pintype "passive"))
      (node (ref "C23") (pin "1") (pinfunction "1_1") (pintype "passive"))
      (node (ref "C25") (pin "1") (pinfunction "1_1") (pintype "passive"))
      (node (ref "C26") (pin "1") (pinfunction "1_1") (pintype "passive"))
      (node (ref "C3") (pin "1") (pinfunction "1_1") (pintype "passive"))
      (node (ref "C33") (pin "P$1") (pinfunction "1_P$1") (pintype "passive"))
      (node (ref "C4") (pin "1") (pinfunction "1_1") (pintype "passive"))
      (node (ref "C9") (pin "1") (pinfunction "1_1") (pintype "passive"))
      (node (ref "D13") (pin "1") (pinfunction "C_1") (pintype "passive"))
      (node (ref "J3") (pin "3") (pinfunction "3_3") (pintype "passive"))
      (node (ref "R1") (pin "2") (pinfunction "2_2") (pintype "passive"))
      (node (ref "R11") (pin "2") (pinfunction "2_2") (pintype "passive"))
      (node (ref "R13") (pin "2") (pinfunction "2_2") (pintype "passive"))
      (node (ref "R16") (pin "1") (pinfunction "1_1") (pintype "passive"))
      (node (ref "R19") (pin "2") (pinfunction "2_2") (pintype "passive"))
      (node (ref "R20") (pin "2") (pinfunction "2_2") (pintype "passive"))
      (node (ref "R24") (pin "2") (pinfunction "2_2") (pintype "passive"))
      (node (ref "R36") (pin "2") (pinfunction "2_2") (pintype "passive"))
      (node (ref "R37") (pin "2") (pinfunction "2_2") (pintype "passive"))
      (node (ref "R40") (pin "1") (pinfunction "1_1") (pintype "passive"))
      (node (ref "R41") (pin "2") (pinfunction "2_2") (pintype "passive"))
      (node (ref "R42") (pin "2") (pinfunction "2_2") (pintype "passive"))
      (node (ref "U0") (pin "17") (pinfunction "VDDIO_17") (pintype "power_in"))
      (node (ref "U0") (pin "36") (pinfunction "VDDIO_36") (pintype "power_in"))
      (node (ref "U0") (pin "44") (pinfunction "VDDIN_44") (pintype "power_in"))
      (node (ref "U1") (pin "2") (pinfunction "VDD_2") (pintype "bidirectional"))
      (node (ref "U3") (pin "18") (pinfunction "VDD_18") (pintype "bidirectional"))
      (node (ref "U4") (pin "8") (pinfunction "VOUT_8") (pintype "power_in"))
      (node (ref "U5") (pin "1") (pinfunction "VCCA_1") (pintype "power_in"))
      (node (ref "U7") (pin "13") (pinfunction "VDD_13") (pintype "bidirectional"))
      (node (ref "U7") (pin "8") (pinfunction "VDDIO_8") (pintype "bidirectional"))
    )
    (net (code "2") (name "+5V") (class "Default")
      (node (ref "C12") (pin "1") (pinfunction "1_1") (pintype "passive"))
      (node (ref "C13") (pin "1") (pinfunction "1_1") (pintype "passive"))
      (node (ref "C16") (pin "1") (pinfunction "1_1") (pintype "passive"))
      (node (ref "C19") (pin "1") (pinfunction "1_1") (pintype "passive"))
      (node (ref "R18") (pin "2") (pinfunction "2_2") (pintype "passive"))
      (node (ref "R23") (pin "2") (pinfunction "2_2") (pintype "passive"))
      (node (ref "R6") (pin "2") (pinfunction "2_2") (pintype "passive"))
      (node (ref "R8") (pin "2") (pinfunction "2_2") (pintype "passive"))
      (node (ref "U2") (pin "3") (pinfunction "VCC_3") (pintype "bidirectional"))
      (node (ref "U5") (pin "14") (pinfunction "VCCB_14") (pintype "power_in"))
      (node (ref "U6") (pin "8") (pinfunction "VOUT_8") (pintype "power_in"))
    )
    (net (code "3") (name "+5V{slash}1") (class "Default")
      (node (ref "C10") (pin "1") (pinfunction "1_1") (pintype "passive"))
      (node (ref "C11") (pin "1") (pinfunction "1_1") (pintype "passive"))
      (node (ref "D10") (pin "1") (pinfunction "C_1") (pintype "passive"))
      (node (ref "D6") (pin "2") (pinfunction "C2_2") (pintype "passive"))
      (node (ref "D7") (pin "2") (pinfunction "C2_2") (pintype "passive"))
      (node (ref "D8") (pin "2") (pinfunction "C2_2") (pintype "passive"))
      (node (ref "RHSM1") (pin "2") (pinfunction "2_2") (pintype "passive"))
      (node (ref "RHSM2") (pin "2") (pinfunction "2_2") (pintype "passive"))
      (node (ref "RHSM3") (pin "2") (pinfunction "2_2") (pintype "passive"))
      (node (ref "U8") (pin "P6") (pinfunction "VDD_P6") (pintype "bidirectional"))
    )
    (net (code "4") (name "+12V") (class "Default")
      (node (ref "C36") (pin "1") (pinfunction "1_1") (pintype "passive"))
      (node (ref "C37") (pin "1") (pinfunction "1_1") (pintype "passive"))
      (node (ref "D1") (pin "2") (pinfunction "C2_2") (pintype "passive"))
      (node (ref "D14") (pin "2") (pinfunction "A_2") (pintype "passive"))
      (node (ref "J1") (pin "1") (pinfunction "1_1") (pintype "passive"))
      (node (ref "J2") (pin "8") (pinfunction "8_8") (pintype "passive"))
      (node (ref "R25") (pin "1") (pinfunction "1_1") (pintype "passive"))
    )
    (net (code "5") (name "+M1TEMP") (class "Default")
      (node (ref "J2") (pin "6") (pinfunction "6_6") (pintype "passive"))
      (node (ref "J3") (pin "1") (pinfunction "1_1") (pintype "passive"))
    )
    (net (code "6") (name "+VBUS") (class "Default")
      (node (ref "D12") (pin "1") (pinfunction "C_1") (pintype "passive"))
      (node (ref "R25") (pin "2") (pinfunction "2_2") (pintype "passive"))
    )
    (net (code "7") (name "-M1TEMP") (class "Default")
      (node (ref "J2") (pin "7") (pinfunction "7_7") (pintype "passive"))
      (node (ref "J3") (pin "2") (pinfunction "2_2") (pintype "passive"))
    )
    (net (code "8") (name "-M2TEMP") (class "Default")
      (node (ref "C38") (pin "1") (pinfunction "1_1") (pintype "passive"))
      (node (ref "J3") (pin "4") (pinfunction "4_4") (pintype "passive"))
      (node (ref "R27") (pin "1") (pinfunction "1_1") (pintype "passive"))
    )
    (net (code "9") (name "12VIN") (class "Default")
      (node (ref "C20") (pin "1") (pinfunction "1_1") (pintype "passive"))
      (node (ref "C27") (pin "1") (pinfunction "1_1") (pintype "passive"))
      (node (ref "C29") (pin "1") (pinfunction "1_1") (pintype "passive"))
      (node (ref "C34") (pin "1") (pinfunction "1_1") (pintype "passive"))
      (node (ref "D14") (pin "1") (pinfunction "C_1") (pintype "passive"))
      (node (ref "R12") (pin "2") (pinfunction "2_2") (pintype "passive"))
      (node (ref "R22") (pin "2") (pinfunction "2_2") (pintype "passive"))
      (node (ref "U4") (pin "1") (pinfunction "VIN_1") (pintype "power_in"))
      (node (ref "U6") (pin "1") (pinfunction "VIN_1") (pintype "power_in"))
    )
    (net (code "10") (name "AGND") (class "Default")
      (node (ref "C1") (pin "2") (pinfunction "2_2") (pintype "passive"))
      (node (ref "C24") (pin "2") (pinfunction "2_2") (pintype "passive"))
      (node (ref "C38") (pin "2") (pinfunction "2_2") (pintype "passive"))
      (node (ref "D1") (pin "1") (pinfunction "A1_1") (pintype "passive"))
      (node (ref "J1") (pin "4") (pinfunction "4_4") (pintype "passive"))
      (node (ref "R15") (pin "2") (pinfunction "2_2") (pintype "passive"))
      (node (ref "R17") (pin "2") (pinfunction "2_2") (pintype "passive"))
      (node (ref "R27") (pin "2") (pinfunction "2_2") (pintype "passive"))
      (node (ref "U0") (pin "5") (pinfunction "GNDA_5") (pintype "power_in"))
    )
    (net (code "11") (name "CANH") (class "Default")
      (node (ref "J2") (pin "4") (pinfunction "4_4") (pintype "passive"))
      (node (ref "SJ1") (pin "2") (pinfunction "2_2") (pintype "passive"))
      (node (ref "U$2") (pin "2") (pinfunction "P2_2") (pintype "bidirectional"))
      (node (ref "U2") (pin "7") (pinfunction "CANH_7") (pintype "bidirectional"))
    )
    (net (code "12") (name "CANL") (class "Default")
      (node (ref "J2") (pin "5") (pinfunction "5_5") (pintype "passive"))
      (node (ref "SJ2") (pin "2") (pinfunction "2_2") (pintype "passive"))
      (node (ref "U$2") (pin "1") (pinfunction "P1_1") (pintype "bidirectional"))
      (node (ref "U2") (pin "6") (pinfunction "CANL_6") (pintype "bidirectional"))
    )
    (net (code "13") (name "CAN_RX_3V3") (class "Default")
      (node (ref "RX2") (pin "C") (pinfunction "C_C") (pintype "passive"))
      (node (ref "U3") (pin "20") (pinfunction "RXCAN_20") (pintype "bidirectional"))
      (node (ref "U5") (pin "3") (pinfunction "A2_3") (pintype "bidirectional"))
    )
    (net (code "14") (name "CAN_RX_5V") (class "Default")
      (node (ref "U2") (pin "4") (pinfunction "RXD_4") (pintype "bidirectional"))
      (node (ref "U5") (pin "12") (pinfunction "B2_12") (pintype "bidirectional"))
    )
    (net (code "15") (name "CAN_TX_3V3") (class "Default")
      (node (ref "TX2") (pin "C") (pinfunction "C_C") (pintype "passive"))
      (node (ref "U3") (pin "19") (pinfunction "TXCAN_19") (pintype "bidirectional"))
      (node (ref "U5") (pin "2") (pinfunction "A1_2") (pintype "bidirectional"))
    )
    (net (code "16") (name "CAN_TX_5V") (class "Default")
      (node (ref "U2") (pin "1") (pinfunction "TXD_1") (pintype "bidirectional"))
      (node (ref "U5") (pin "13") (pinfunction "B1_13") (pintype "bidirectional"))
    )
    (net (code "17") (name "CSQ") (class "Default")
      (node (ref "J2") (pin "10") (pinfunction "10_10") (pintype "passive"))
      (node (ref "R32") (pin "2") (pinfunction "2_2") (pintype "passive"))
    )
    (net (code "18") (name "DATA") (class "Default")
      (node (ref "J2") (pin "11") (pinfunction "11_11") (pintype "passive"))
      (node (ref "R34") (pin "2") (pinfunction "2_2") (pintype "passive"))
    )
    (net (code "19") (name "GND") (class "Default")
      (node (ref "C15") (pin "2") (pinfunction "2_2") (pintype "passive"))
      (node (ref "C17") (pin "2") (pinfunction "2_2") (pintype "passive"))
      (node (ref "C18") (pin "2") (pinfunction "2_2") (pintype "passive"))
      (node (ref "C2") (pin "2") (pinfunction "2_2") (pintype "passive"))
      (node (ref "C23") (pin "2") (pinfunction "2_2") (pintype "passive"))
      (node (ref "C25") (pin "2") (pinfunction "2_2") (pintype "passive"))
      (node (ref "C26") (pin "2") (pinfunction "2_2") (pintype "passive"))
      (node (ref "C27") (pin "2") (pinfunction "2_2") (pintype "passive"))
      (node (ref "C28") (pin "2") (pinfunction "2_2") (pintype "passive"))
      (node (ref "C29") (pin "2") (pinfunction "2_2") (pintype "passive"))
      (node (ref "C3") (pin "2") (pinfunction "2_2") (pintype "passive"))
      (node (ref "C30") (pin "2") (pinfunction "2_2") (pintype "passive"))
      (node (ref "C31") (pin "P$2") (pinfunction "2_P$2") (pintype "passive"))
      (node (ref "C33") (pin "P$2") (pinfunction "2_P$2") (pintype "passive"))
      (node (ref "C36") (pin "2") (pinfunction "2_2") (pintype "passive"))
      (node (ref "C37") (pin "2") (pinfunction "2_2") (pintype "passive"))
      (node (ref "C4") (pin "2") (pinfunction "2_2") (pintype "passive"))
      (node (ref "C5") (pin "2") (pinfunction "2_2") (pintype "passive"))
      (node (ref "C6") (pin "2") (pinfunction "2_2") (pintype "passive"))
      (node (ref "C7") (pin "2") (pinfunction "2_2") (pintype "passive"))
      (node (ref "C9") (pin "2") (pinfunction "2_2") (pintype "passive"))
      (node (ref "D2") (pin "C") (pinfunction "C_C") (pintype "passive"))
      (node (ref "D3") (pin "C") (pinfunction "C_C") (pintype "passive"))
      (node (ref "D5") (pin "C") (pinfunction "C_C") (pintype "passive"))
      (node (ref "J2") (pin "2") (pinfunction "2_2") (pintype "passive"))
      (node (ref "J2") (pin "3") (pinfunction "3_3") (pintype "passive"))
      (node (ref "R17") (pin "1") (pinfunction "1_1") (pintype "passive"))
      (node (ref "R21") (pin "1") (pinfunction "1_1") (pintype "passive"))
      (node (ref "R7") (pin "2") (pinfunction "2_2") (pintype "passive"))
      (node (ref "TC-JTAG2") (pin "3") (pinfunction "3_3") (pintype "passive"))
      (node (ref "U0") (pin "18") (pinfunction "GND_18") (pintype "power_in"))
      (node (ref "U0") (pin "35") (pinfunction "GND_35") (pintype "power_in"))
      (node (ref "U0") (pin "42") (pinfunction "GND_42") (pintype "power_in"))
      (node (ref "U0") (pin "THERMAL") (pinfunction "GND_THERMAL") (pintype "power_in"))
      (node (ref "U1") (pin "1") (pinfunction "GND_1") (pintype "bidirectional"))
      (node (ref "U3") (pin "21") (pinfunction "VSS_21") (pintype "bidirectional"))
      (node (ref "U3") (pin "8") (pinfunction "VSS_8") (pintype "bidirectional"))
      (node (ref "U4") (pin "5") (pinfunction "GND_5") (pintype "power_in"))
      (node (ref "U5") (pin "7") (pinfunction "GND_7") (pintype "power_in"))
      (node (ref "U7") (pin "18") (pinfunction "GND_18") (pintype "bidirectional"))
      (node (ref "U7") (pin "19") (pinfunction "INT2_19") (pintype "bidirectional"))
      (node (ref "U7") (pin "20") (pinfunction "GND_20") (pintype "bidirectional"))
      (node (ref "Y1") (pin "2") (pinfunction "2_2") (pintype "passive"))
    )
    (net (code "20") (name "GND1") (class "Default")
      (node (ref "C10") (pin "2") (pinfunction "2_2") (pintype "passive"))
      (node (ref "C11") (pin "2") (pinfunction "2_2") (pintype "passive"))
      (node (ref "C14") (pin "2") (pinfunction "2_2") (pintype "passive"))
      (node (ref "C21") (pin "2") (pinfunction "2_2") (pintype "passive"))
      (node (ref "C22") (pin "2") (pinfunction "2_2") (pintype "passive"))
      (node (ref "D6") (pin "1") (pinfunction "A1_1") (pintype "passive"))
      (node (ref "D7") (pin "1") (pinfunction "A1_1") (pintype "passive"))
      (node (ref "D8") (pin "1") (pinfunction "A1_1") (pintype "passive"))
      (node (ref "J2") (pin "16") (pinfunction "16_16") (pintype "passive"))
      (node (ref "U8") (pin "P7") (pinfunction "GND_P7") (pintype "bidirectional"))
    )
    (net (code "21") (name "GND_CAN") (class "Default")
      (node (ref "C12") (pin "2") (pinfunction "2_2") (pintype "passive"))
      (node (ref "C13") (pin "2") (pinfunction "2_2") (pintype "passive"))
      (node (ref "C16") (pin "2") (pinfunction "2_2") (pintype "passive"))
      (node (ref "C19") (pin "2") (pinfunction "2_2") (pintype "passive"))
      (node (ref "C20") (pin "2") (pinfunction "2_2") (pintype "passive"))
      (node (ref "C32") (pin "2") (pinfunction "2_2") (pintype "passive"))
      (node (ref "C34") (pin "2") (pinfunction "2_2") (pintype "passive"))
      (node (ref "C35") (pin "2") (pinfunction "2_2") (pintype "passive"))
      (node (ref "C8") (pin "2") (pinfunction "2_2") (pintype "passive"))
      (node (ref "D4") (pin "C") (pinfunction "C_C") (pintype "passive"))
      (node (ref "R39") (pin "2") (pinfunction "2_2") (pintype "passive"))
      (node (ref "R7") (pin "1") (pinfunction "1_1") (pintype "passive"))
      (node (ref "R9") (pin "1") (pinfunction "1_1") (pintype "passive"))
      (node (ref "U$2") (pin "3") (pinfunction "P3_3") (pintype "bidirectional"))
      (node (ref "U2") (pin "2") (pinfunction "GND_2") (pintype "bidirectional"))
      (node (ref "U2") (pin "9") (pinfunction "GND_9") (pintype "bidirectional"))
      (node (ref "U6") (pin "5") (pinfunction "GND_5") (pintype "power_in"))
    )
    (net (code "22") (name "IFA") (class "Default")
      (node (ref "C14") (pin "1") (pinfunction "1_1") (pintype "passive"))
      (node (ref "D8") (pin "3") (pinfunction "C1A2_3") (pintype "passive"))
      (node (ref "J2") (pin "12") (pinfunction "12_12") (pintype "passive"))
      (node (ref "R29") (pin "2") (pinfunction "2_2") (pintype "passive"))
    )
    (net (code "23") (name "IFB") (class "Default")
      (node (ref "C21") (pin "1") (pinfunction "1_1") (pintype "passive"))
      (node (ref "D7") (pin "3") (pinfunction "C1A2_3") (pintype "passive"))
      (node (ref "J2") (pin "13") (pinfunction "13_13") (pintype "passive"))
      (node (ref "R30") (pin "2") (pinfunction "2_2") (pintype "passive"))
    )
    (net (code "24") (name "IFC") (class "Default")
      (node (ref "C22") (pin "1") (pinfunction "1_1") (pintype "passive"))
      (node (ref "D6") (pin "3") (pinfunction "C1A2_3") (pintype "passive"))
      (node (ref "J2") (pin "14") (pinfunction "14_14") (pintype "passive"))
      (node (ref "R31") (pin "2") (pinfunction "2_2") (pintype "passive"))
    )
    (net (code "25") (name "NC1") (class "Default")
      (node (ref "J1") (pin "3") (pinfunction "3_3") (pintype "passive"))
    )
    (net (code "26") (name "Net-(C8-Pad1)") (class "Default")
      (node (ref "C8") (pin "1") (pinfunction "1_1") (pintype "passive"))
      (node (ref "R4") (pin "1") (pinfunction "1_1") (pintype "passive"))
      (node (ref "R5") (pin "2") (pinfunction "2_2") (pintype "passive"))
      (node (ref "SJ3") (pin "1") (pinfunction "1_1") (pintype "passive"))
    )
    (net (code "27") (name "Net-(C31-1)") (class "Default")
      (node (ref "C31") (pin "P$1") (pinfunction "1_P$1") (pintype "passive"))
      (node (ref "U7") (pin "10") (pinfunction "REGOUT_10") (pintype "bidirectional"))
    )
    (net (code "28") (name "Net-(D2-PadA)") (class "Default")
      (node (ref "D2") (pin "A") (pinfunction "A_A") (pintype "passive"))
      (node (ref "R3") (pin "1") (pinfunction "1_1") (pintype "passive"))
    )
    (net (code "29") (name "Net-(D3-PadA)") (class "Default")
      (node (ref "D3") (pin "A") (pinfunction "A_A") (pintype "passive"))
      (node (ref "R2") (pin "1") (pinfunction "1_1") (pintype "passive"))
    )
    (net (code "30") (name "Net-(D4-PadA)") (class "Default")
      (node (ref "D4") (pin "A") (pinfunction "A_A") (pintype "passive"))
      (node (ref "R23") (pin "1") (pinfunction "1_1") (pintype "passive"))
    )
    (net (code "31") (name "Net-(D5-PadA)") (class "Default")
      (node (ref "D5") (pin "A") (pinfunction "A_A") (pintype "passive"))
      (node (ref "R1") (pin "1") (pinfunction "1_1") (pintype "passive"))
    )
    (net (code "32") (name "Net-(D13-A)") (class "Default")
      (node (ref "D13") (pin "2") (pinfunction "A_2") (pintype "passive"))
      (node (ref "TC-JTAG2") (pin "10") (pinfunction "10_10") (pintype "passive"))
    )
    (net (code "33") (name "Net-(R4-Pad2)") (class "Default")
      (node (ref "R4") (pin "2") (pinfunction "2_2") (pintype "passive"))
      (node (ref "SJ1") (pin "3") (pinfunction "3_3") (pintype "passive"))
    )
    (net (code "34") (name "Net-(R5-Pad1)") (class "Default")
      (node (ref "R5") (pin "1") (pinfunction "1_1") (pintype "passive"))
      (node (ref "SJ2") (pin "1") (pinfunction "1_1") (pintype "passive"))
    )
    (net (code "35") (name "Net-(R26-Pad1)") (class "Default")
      (node (ref "R26") (pin "1") (pinfunction "1_1") (pintype "passive"))
      (node (ref "SJ2") (pin "3") (pinfunction "3_3") (pintype "passive"))
    )
    (net (code "36") (name "Net-(R26-Pad2)") (class "Default")
      (node (ref "R26") (pin "2") (pinfunction "2_2") (pintype "passive"))
      (node (ref "SJ1") (pin "1") (pinfunction "1_1") (pintype "passive"))
    )
    (net (code "37") (name "Net-(R36-Pad1)") (class "Default")
      (node (ref "R36") (pin "1") (pinfunction "1_1") (pintype "passive"))
      (node (ref "RX2") (pin "A") (pinfunction "A_A") (pintype "passive"))
    )
    (net (code "38") (name "Net-(R37-Pad1)") (class "Default")
      (node (ref "R37") (pin "1") (pinfunction "1_1") (pintype "passive"))
      (node (ref "TX2") (pin "A") (pinfunction "A_A") (pintype "passive"))
    )
    (net (code "39") (name "Net-(U0-PA00{slash}EINT0{slash}SERCOM1.0)") (class "Default")
      (node (ref "C5") (pin "1") (pinfunction "1_1") (pintype "passive"))
      (node (ref "U0") (pin "1") (pinfunction "PA00/EINT0/SERCOM1.0_1") (pintype "bidirectional"))
      (node (ref "X1") (pin "P$1") (pinfunction "P$1_P$1") (pintype "bidirectional"))
    )
    (net (code "40") (name "Net-(U0-PA01{slash}EINT1{slash}SERCOM1.1)") (class "Default")
      (node (ref "C6") (pin "1") (pinfunction "1_1") (pintype "passive"))
      (node (ref "U0") (pin "2") (pinfunction "PA01/EINT1/SERCOM1.1_2") (pintype "bidirectional"))
      (node (ref "X1") (pin "P$2") (pinfunction "P$2_P$2") (pintype "bidirectional"))
    )
    (net (code "41") (name "Net-(U0-VDDA)") (class "Default")
      (node (ref "C1") (pin "1") (pinfunction "1_1") (pintype "passive"))
      (node (ref "R16") (pin "2") (pinfunction "2_2") (pintype "passive"))
      (node (ref "U0") (pin "6") (pinfunction "VDDA_6") (pintype "power_in"))
    )
    (net (code "42") (name "Net-(U0-VDDCORE)") (class "Default")
      (node (ref "C7") (pin "1") (pinfunction "1_1") (pintype "passive"))
      (node (ref "U0") (pin "43") (pinfunction "VDDCORE_43") (pintype "power_in"))
    )
    (net (code "43") (name "Net-(U2-RS)") (class "Default")
      (node (ref "R39") (pin "1") (pinfunction "1_1") (pintype "passive"))
      (node (ref "U2") (pin "8") (pinfunction "RS_8") (pintype "bidirectional"))
    )
    (net (code "44") (name "Net-(U2-SPLIT)") (class "Default")
      (node (ref "SJ3") (pin "2") (pinfunction "2_2") (pintype "passive"))
      (node (ref "U2") (pin "5") (pinfunction "SPLIT_5") (pintype "bidirectional"))
    )
    (net (code "45") (name "Net-(U3-OSC1)") (class "Default")
      (node (ref "C15") (pin "1") (pinfunction "1_1") (pintype "passive"))
      (node (ref "U3") (pin "7") (pinfunction "OSC1_7") (pintype "bidirectional"))
      (node (ref "Y1") (pin "1") (pinfunction "1_1") (pintype "passive"))
    )
    (net (code "46") (name "Net-(U3-OSC2)") (class "Default")
      (node (ref "C17") (pin "1") (pinfunction "1_1") (pintype "passive"))
      (node (ref "U3") (pin "6") (pinfunction "OSC2_6") (pintype "bidirectional"))
      (node (ref "Y1") (pin "3") (pinfunction "3_3") (pintype "passive"))
    )
    (net (code "47") (name "Net-(U3-~{RST})") (class "Default")
      (node (ref "R41") (pin "1") (pinfunction "1_1") (pintype "passive"))
      (node (ref "U3") (pin "17") (pinfunction "~{RST}_17") (pintype "bidirectional"))
    )
    (net (code "48") (name "Net-(U3-~{TX0RTS})") (class "Default")
      (node (ref "R40") (pin "2") (pinfunction "2_2") (pintype "passive"))
      (node (ref "U3") (pin "2") (pinfunction "~{TX0RTS}_2") (pintype "bidirectional"))
      (node (ref "U3") (pin "3") (pinfunction "~{TX1RTS}_3") (pintype "bidirectional"))
      (node (ref "U3") (pin "5") (pinfunction "~{TX2RTS}_5") (pintype "bidirectional"))
    )
    (net (code "49") (name "Net-(U4-CT)") (class "Default")
      (node (ref "C28") (pin "1") (pinfunction "1_1") (pintype "passive"))
      (node (ref "U4") (pin "4") (pinfunction "CT_4") (pintype "passive"))
    )
    (net (code "50") (name "Net-(U4-PG)") (class "Default")
      (node (ref "R19") (pin "1") (pinfunction "1_1") (pintype "passive"))
      (node (ref "U4") (pin "6") (pinfunction "PG_6") (pintype "open_collector"))
    )
    (net (code "51") (name "Net-(U4-SI)") (class "Default")
      (node (ref "C30") (pin "1") (pinfunction "1_1") (pintype "passive"))
      (node (ref "R21") (pin "2") (pinfunction "2_2") (pintype "passive"))
      (node (ref "R22") (pin "1") (pinfunction "1_1") (pintype "passive"))
      (node (ref "U4") (pin "2") (pinfunction "SI_2") (pintype "input"))
    )
    (net (code "52") (name "Net-(U4-SO)") (class "Default")
      (node (ref "R20") (pin "1") (pinfunction "1_1") (pintype "passive"))
      (node (ref "U4") (pin "7") (pinfunction "SO_7") (pintype "output"))
    )
    (net (code "53") (name "Net-(U5-OE)") (class "Default")
      (node (ref "R6") (pin "1") (pinfunction "1_1") (pintype "passive"))
      (node (ref "U5") (pin "8") (pinfunction "OE_8") (pintype "output"))
    )
    (net (code "54") (name "Net-(U6-CT)") (class "Default")
      (node (ref "C32") (pin "1") (pinfunction "1_1") (pintype "passive"))
      (node (ref "U6") (pin "4") (pinfunction "CT_4") (pintype "passive"))
    )
    (net (code "55") (name "Net-(U6-PG)") (class "Default")
      (node (ref "R8") (pin "1") (pinfunction "1_1") (pintype "passive"))
      (node (ref "U6") (pin "6") (pinfunction "PG_6") (pintype "open_collector"))
    )
    (net (code "56") (name "Net-(U6-SI)") (class "Default")
      (node (ref "C35") (pin "1") (pinfunction "1_1") (pintype "passive"))
      (node (ref "R12") (pin "1") (pinfunction "1_1") (pintype "passive"))
      (node (ref "R9") (pin "2") (pinfunction "2_2") (pintype "passive"))
      (node (ref "U6") (pin "2") (pinfunction "SI_2") (pintype "input"))
    )
    (net (code "57") (name "Net-(U6-SO)") (class "Default")
      (node (ref "R18") (pin "1") (pinfunction "1_1") (pintype "passive"))
      (node (ref "U6") (pin "7") (pinfunction "SO_7") (pintype "output"))
    )
    (net (code "58") (name "Net-(U8-CSQ)") (class "Default")
      (node (ref "R32") (pin "1") (pinfunction "1_1") (pintype "passive"))
      (node (ref "U8") (pin "P3") (pinfunction "CSQ_P3") (pintype "bidirectional"))
    )
    (net (code "59") (name "Net-(U8-DATA)") (class "Default")
      (node (ref "R34") (pin "1") (pinfunction "1_1") (pintype "passive"))
      (node (ref "U8") (pin "P4") (pinfunction "DATA_P4") (pintype "bidirectional"))
    )
    (net (code "60") (name "Net-(U8-IFA)") (class "Default")
      (node (ref "R29") (pin "1") (pinfunction "1_1") (pintype "passive"))
      (node (ref "RHSM1") (pin "1") (pinfunction "1_1") (pintype "passive"))
      (node (ref "U8") (pin "P5") (pinfunction "IFA_P5") (pintype "bidirectional"))
    )
    (net (code "61") (name "Net-(U8-IFB)") (class "Default")
      (node (ref "R30") (pin "1") (pinfunction "1_1") (pintype "passive"))
      (node (ref "RHSM2") (pin "1") (pinfunction "1_1") (pintype "passive"))
      (node (ref "U8") (pin "P8") (pinfunction "IFB_P8") (pintype "bidirectional"))
    )
    (net (code "62") (name "Net-(U8-IFC)") (class "Default")
      (node (ref "R31") (pin "1") (pinfunction "1_1") (pintype "passive"))
      (node (ref "RHSM3") (pin "1") (pinfunction "1_1") (pintype "passive"))
      (node (ref "U8") (pin "P1") (pinfunction "IFC_P1") (pintype "bidirectional"))
    )
    (net (code "63") (name "Net-(U8-SCK)") (class "Default")
      (node (ref "R33") (pin "1") (pinfunction "1_1") (pintype "passive"))
      (node (ref "U8") (pin "P2") (pinfunction "SCK_P2") (pintype "bidirectional"))
    )
    (net (code "64") (name "PA04{slash}A3") (class "Default")
      (node (ref "U0") (pin "9") (pinfunction "PA04/EINT4/VREFB/AIN4/SERCOM0.0_9") (pintype "bidirectional"))
    )
    (net (code "65") (name "PA05{slash}A4-PSR") (class "Default")
      (node (ref "C24") (pin "1") (pinfunction "1_1") (pintype "passive"))
      (node (ref "R10") (pin "2") (pinfunction "2_2") (pintype "passive"))
      (node (ref "R14") (pin "2") (pinfunction "2_2") (pintype "passive"))
      (node (ref "R15") (pin "1") (pinfunction "1_1") (pintype "passive"))
      (node (ref "U0") (pin "10") (pinfunction "PA05/EINT5/AIN5/SERCOM0.1_10") (pintype "bidirectional"))
    )
    (net (code "66") (name "PA06{slash}D8-LED1") (class "Default")
      (node (ref "R3") (pin "2") (pinfunction "2_2") (pintype "passive"))
      (node (ref "U0") (pin "11") (pinfunction "PA06/EINT6/AIN6/SERCOM0.2_11") (pintype "bidirectional"))
    )
    (net (code "67") (name "PA07{slash}D9-LED2") (class "Default")
      (node (ref "R2") (pin "2") (pinfunction "2_2") (pintype "passive"))
      (node (ref "U0") (pin "12") (pinfunction "PA07/I7/AIN7/SERCOM0.3/I2SD0_12") (pintype "bidirectional"))
    )
    (net (code "68") (name "PA10{slash}TX1") (class "Default")
      (node (ref "U0") (pin "15") (pinfunction "PA10/I10/AIN18/SERCOM0+2.2/I2SCK_15") (pintype "bidirectional"))
    )
    (net (code "69") (name "PA11{slash}RX1") (class "Default")
      (node (ref "U0") (pin "16") (pinfunction "PA11/I11/AIN19/SERCOM0+2.3/I2SF0_16") (pintype "bidirectional"))
    )
    (net (code "70") (name "PA12{slash}MISO") (class "Default")
      (node (ref "U0") (pin "21") (pinfunction "PA12/I12/I2C/SERCOM2+4.0_21") (pintype "bidirectional"))
      (node (ref "U3") (pin "15") (pinfunction "SO_15") (pintype "bidirectional"))
      (node (ref "U7") (pin "9") (pinfunction "AD0/SD0_9") (pintype "bidirectional"))
    )
    (net (code "71") (name "PA14{slash}D2") (class "Default")
      (node (ref "U0") (pin "23") (pinfunction "PA14/I14/SERCOM2+4.2_23") (pintype "bidirectional"))
    )
    (net (code "72") (name "PA15{slash}D5") (class "Default")
      (node (ref "U0") (pin "24") (pinfunction "PA15/I15/SERCOM3+4.3_24") (pintype "bidirectional"))
    )
    (net (code "73") (name "PA16{slash}D11-CAN_CS") (class "Default")
      (node (ref "R42") (pin "1") (pinfunction "1_1") (pintype "passive"))
      (node (ref "U0") (pin "25") (pinfunction "PA16/I2C/I0/SERCOM1+3.0_25") (pintype "bidirectional"))
      (node (ref "U3") (pin "16") (pinfunction "~{CS}_16") (pintype "bidirectional"))
    )
    (net (code "74") (name "PA17{slash}D13-CAN_IRQ") (class "Default")
      (node (ref "U0") (pin "26") (pinfunction "PA17/I2C/I1/SERCOM1+3.1_26") (pintype "bidirectional"))
      (node (ref "U3") (pin "11") (pinfunction "~{INT}_11") (pintype "bidirectional"))
    )
    (net (code "75") (name "PA18{slash}D10-IMU_INT") (class "Default")
      (node (ref "U0") (pin "27") (pinfunction "PA18/I2/SERCOM1+3.2_27") (pintype "bidirectional"))
      (node (ref "U7") (pin "12") (pinfunction "INT1_12") (pintype "bidirectional"))
    )
    (net (code "76") (name "PA20{slash}D6-IMU_CS") (class "Default")
      (node (ref "U0") (pin "29") (pinfunction "PA20/I4/SERCOM3+5.2/I2SSC_29") (pintype "bidirectional"))
      (node (ref "U7") (pin "22") (pinfunction "~{CS}_22") (pintype "bidirectional"))
    )
    (net (code "77") (name "PA21{slash}D7") (class "Default")
      (node (ref "U0") (pin "30") (pinfunction "PA21/I5/SERCOM3+5.3/I2SFS0_30") (pintype "bidirectional"))
    )
    (net (code "78") (name "PA22{slash}SCL") (class "Default")
      (node (ref "R13") (pin "1") (pinfunction "1_1") (pintype "passive"))
      (node (ref "U0") (pin "31") (pinfunction "PA22/I2C/I6/SERCOM3+5.0_31") (pintype "bidirectional"))
      (node (ref "U1") (pin "3") (pinfunction "SCL_3") (pintype "bidirectional"))
    )
    (net (code "79") (name "PA23{slash}SDA") (class "Default")
      (node (ref "R11") (pin "1") (pinfunction "1_1") (pintype "passive"))
      (node (ref "U0") (pin "32") (pinfunction "PA23/I2C/I7/SERCOM3+5.1/SOF_32") (pintype "bidirectional"))
      (node (ref "U1") (pin "4") (pinfunction "SDA_4") (pintype "bidirectional"))
    )
    (net (code "80") (name "PA24{slash}USBD_N") (class "Default")
      (node (ref "TC-JTAG2") (pin "7") (pinfunction "7_7") (pintype "passive"))
      (node (ref "TC-JTAG2") (pin "8") (pinfunction "8_8") (pintype "passive"))
      (node (ref "U0") (pin "33") (pinfunction "PA24/I12/SERCOM3+5.2/D-_33") (pintype "bidirectional"))
    )
    (net (code "81") (name "PA25{slash}USBD_P") (class "Default")
      (node (ref "TC-JTAG2") (pin "5") (pinfunction "5_5") (pintype "passive"))
      (node (ref "TC-JTAG2") (pin "6") (pinfunction "6_6") (pintype "passive"))
      (node (ref "U0") (pin "34") (pinfunction "PA25/I13/SERCOM3+5.3/D+_34") (pintype "bidirectional"))
    )
    (net (code "82") (name "PA30{slash}SWCLK") (class "Default")
      (node (ref "TC-JTAG2") (pin "2") (pinfunction "2_2") (pintype "passive"))
      (node (ref "U0") (pin "45") (pinfunction "PA30/I10/SECOM1.2/SWCLK_45") (pintype "bidirectional"))
    )
    (net (code "83") (name "PA31{slash}SWDIO") (class "Default")
      (node (ref "TC-JTAG2") (pin "4") (pinfunction "4_4") (pintype "passive"))
      (node (ref "U0") (pin "46") (pinfunction "PA31/I11/SECOM1.3/SWDIO_46") (pintype "bidirectional"))
    )
    (net (code "84") (name "PB02{slash}A5") (class "Default")
      (node (ref "U0") (pin "47") (pinfunction "PB02/I2/AIN10/SERCOM5.0_47") (pintype "bidirectional"))
    )
    (net (code "85") (name "PB08{slash}A1") (class "Default")
      (node (ref "U0") (pin "7") (pinfunction "PB08/I8/AIN2/SERCOM4.0_7") (pintype "bidirectional"))
    )
    (net (code "86") (name "PB09{slash}A2") (class "Default")
      (node (ref "U0") (pin "8") (pinfunction "PB09/I9/AIN3/SERCOM4.1_8") (pintype "bidirectional"))
    )
    (net (code "87") (name "PB10{slash}MOSI") (class "Default")
      (node (ref "U0") (pin "19") (pinfunction "PB10/I10/SERCOM4.2/I2SMC_19") (pintype "bidirectional"))
      (node (ref "U3") (pin "14") (pinfunction "SI_14") (pintype "bidirectional"))
      (node (ref "U7") (pin "24") (pinfunction "SDA/SDI_24") (pintype "bidirectional"))
    )
    (net (code "88") (name "PB11{slash}SCK") (class "Default")
      (node (ref "U0") (pin "20") (pinfunction "PB11/I11/SERCOM4.3/I2SCL_20") (pintype "bidirectional"))
      (node (ref "U3") (pin "12") (pinfunction "SCK_12") (pintype "bidirectional"))
      (node (ref "U7") (pin "23") (pinfunction "SCL/SCLK_23") (pintype "bidirectional"))
    )
    (net (code "89") (name "PB23{slash}D31") (class "Default")
      (node (ref "U0") (pin "38") (pinfunction "PB23/I7/SERCOM5.3_38") (pintype "bidirectional"))
    )
    (net (code "90") (name "PRESSURE") (class "Default")
      (node (ref "J2") (pin "1") (pinfunction "1_1") (pintype "passive"))
      (node (ref "R14") (pin "1") (pinfunction "1_1") (pintype "passive"))
    )
    (net (code "91") (name "PRSR_OUT") (class "Default")
      (node (ref "D1") (pin "3") (pinfunction "C1A2_3") (pintype "passive"))
      (node (ref "J1") (pin "2") (pinfunction "2_2") (pintype "passive"))
      (node (ref "R10") (pin "1") (pinfunction "1_1") (pintype "passive"))
    )
    (net (code "92") (name "RST") (class "Default")
      (node (ref "R24") (pin "1") (pinfunction "1_1") (pintype "passive"))
      (node (ref "TC-JTAG2") (pin "9") (pinfunction "9_9") (pintype "passive"))
      (node (ref "U0") (pin "40") (pinfunction "/RESET_40") (pintype "bidirectional"))
    )
    (net (code "93") (name "SCK") (class "Default")
      (node (ref "J2") (pin "9") (pinfunction "9_9") (pintype "passive"))
      (node (ref "R33") (pin "2") (pinfunction "2_2") (pintype "passive"))
    )
    (net (code "94") (name "_+5V_ENC") (class "Default")
      (node (ref "D10") (pin "2") (pinfunction "A_2") (pintype "passive"))
      (node (ref "J2") (pin "15") (pinfunction "15_15") (pintype "passive"))
    )
    (net (code "95") (name "_+VBUS") (class "Default")
      (node (ref "D12") (pin "2") (pinfunction "A_2") (pintype "passive"))
      (node (ref "TC-JTAG2") (pin "1") (pinfunction "1_1") (pintype "passive"))
    )
    (net (code "96") (name "unconnected-(R28-Pad1)") (class "Default")
      (node (ref "R28") (pin "1") (pinfunction "1_1") (pintype "passive"))
    )
    (net (code "97") (name "unconnected-(R28-Pad2)") (class "Default")
      (node (ref "R28") (pin "2") (pinfunction "2_2") (pintype "passive"))
    )
    (net (code "98") (name "unconnected-(R35-Pad1)") (class "Default")
      (node (ref "R35") (pin "1") (pinfunction "1_1") (pintype "passive"))
    )
    (net (code "99") (name "unconnected-(R35-Pad2)") (class "Default")
      (node (ref "R35") (pin "2") (pinfunction "2_2") (pintype "passive"))
    )
    (net (code "100") (name "unconnected-(R38-Pad1)") (class "Default")
      (node (ref "R38") (pin "1") (pinfunction "1_1") (pintype "passive"))
    )
    (net (code "101") (name "unconnected-(R38-Pad2)") (class "Default")
      (node (ref "R38") (pin "2") (pinfunction "2_2") (pintype "passive"))
    )
    (net (code "102") (name "unconnected-(R43-Pad1)") (class "Default")
      (node (ref "R43") (pin "1") (pinfunction "1_1") (pintype "passive"))
    )
    (net (code "103") (name "unconnected-(R43-Pad2)") (class "Default")
      (node (ref "R43") (pin "2") (pinfunction "2_2") (pintype "passive"))
    )
    (net (code "104") (name "unconnected-(U0-PA02{slash}EINT2{slash}AIN0{slash}Y0{slash}VOUT-Pad3)") (class "Default")
      (node (ref "U0") (pin "3") (pinfunction "PA02/EINT2/AIN0/Y0/VOUT_3") (pintype "bidirectional"))
    )
    (net (code "105") (name "unconnected-(U0-PA03{slash}EINT3{slash}VREFA{slash}AIN1-Pad4)") (class "Default")
      (node (ref "U0") (pin "4") (pinfunction "PA03/EINT3/VREFA/AIN1_4") (pintype "bidirectional"))
    )
    (net (code "106") (name "unconnected-(U0-PA08{slash}I2C{slash}AIN16{slash}SERCOM0+2.0{slash}I2SD1-Pad13)") (class "Default")
      (node (ref "U0") (pin "13") (pinfunction "PA08/I2C/AIN16/SERCOM0+2.0/I2SD1_13") (pintype "bidirectional"))
    )
    (net (code "107") (name "unconnected-(U0-PA09{slash}I2C{slash}I9{slash}AIN17{slash}SERCOM0+2.1{slash}I2SMC-Pad14)") (class "Default")
      (node (ref "U0") (pin "14") (pinfunction "PA09/I2C/I9/AIN17/SERCOM0+2.1/I2SMC_14") (pintype "bidirectional"))
    )
    (net (code "108") (name "unconnected-(U0-PA13{slash}I13{slash}I2C{slash}SERCOM2+4.1-Pad22)") (class "Default")
      (node (ref "U0") (pin "22") (pinfunction "PA13/I13/I2C/SERCOM2+4.1_22") (pintype "bidirectional"))
    )
    (net (code "109") (name "unconnected-(U0-PA19{slash}I3{slash}SERCOM1+3.3{slash}I2SD0-Pad28)") (class "Default")
      (node (ref "U0") (pin "28") (pinfunction "PA19/I3/SERCOM1+3.3/I2SD0_28") (pintype "bidirectional"))
    )
    (net (code "110") (name "unconnected-(U0-PA27{slash}I15-Pad39)") (class "Default")
      (node (ref "U0") (pin "39") (pinfunction "PA27/I15_39") (pintype "bidirectional"))
    )
    (net (code "111") (name "unconnected-(U0-PA28{slash}I8-Pad41)") (class "Default")
      (node (ref "U0") (pin "41") (pinfunction "PA28/I8_41") (pintype "bidirectional"))
    )
    (net (code "112") (name "unconnected-(U0-PB03{slash}I3{slash}AIN11{slash}SERCOM5.1-Pad48)") (class "Default")
      (node (ref "U0") (pin "48") (pinfunction "PB03/I3/AIN11/SERCOM5.1_48") (pintype "bidirectional"))
    )
    (net (code "113") (name "unconnected-(U0-PB22{slash}I6{slash}SERCOM5.2-Pad37)") (class "Default")
      (node (ref "U0") (pin "37") (pinfunction "PB22/I6/SERCOM5.2_37") (pintype "bidirectional"))
    )
    (net (code "114") (name "unconnected-(U3-CLKOUT{slash}SOF-Pad1)") (class "Default")
      (node (ref "U3") (pin "1") (pinfunction "CLKOUT/SOF_1") (pintype "bidirectional"))
    )
    (net (code "115") (name "unconnected-(U3-~{RX0BF}-Pad10)") (class "Default")
      (node (ref "U3") (pin "10") (pinfunction "~{RX0BF}_10") (pintype "bidirectional"))
    )
    (net (code "116") (name "unconnected-(U3-~{RX1BF}-Pad9)") (class "Default")
      (node (ref "U3") (pin "9") (pinfunction "~{RX1BF}_9") (pintype "bidirectional"))
    )
    (net (code "117") (name "unconnected-(U4-NC-Pad3)") (class "Default")
      (node (ref "U4") (pin "3") (pinfunction "NC_3") (pintype "passive"))
    )
    (net (code "118") (name "unconnected-(U5-A3-Pad4)") (class "Default")
      (node (ref "U5") (pin "4") (pinfunction "A3_4") (pintype "bidirectional"))
    )
    (net (code "119") (name "unconnected-(U5-A4-Pad5)") (class "Default")
      (node (ref "U5") (pin "5") (pinfunction "A4_5") (pintype "bidirectional"))
    )
    (net (code "120") (name "unconnected-(U5-B3-Pad11)") (class "Default")
      (node (ref "U5") (pin "11") (pinfunction "B3_11") (pintype "bidirectional"))
    )
    (net (code "121") (name "unconnected-(U5-B4-Pad10)") (class "Default")
      (node (ref "U5") (pin "10") (pinfunction "B4_10") (pintype "bidirectional"))
    )
    (net (code "122") (name "unconnected-(U5-EPAD-Pad15)") (class "Default")
      (node (ref "U5") (pin "15") (pinfunction "EPAD_15") (pintype "passive"))
    )
    (net (code "123") (name "unconnected-(U5-NC-Pad9)") (class "Default")
      (node (ref "U5") (pin "9") (pinfunction "NC_9") (pintype "passive"))
    )
    (net (code "124") (name "unconnected-(U5-NC_2-Pad6)") (class "Default")
      (node (ref "U5") (pin "6") (pinfunction "NC_2_6") (pintype "passive"))
    )
    (net (code "125") (name "unconnected-(U6-NC-Pad3)") (class "Default")
      (node (ref "U6") (pin "3") (pinfunction "NC_3") (pintype "passive"))
    )
    (net (code "126") (name "unconnected-(U7-AUX_CL-Pad7)") (class "Default")
      (node (ref "U7") (pin "7") (pinfunction "AUX_CL_7") (pintype "bidirectional"))
    )
    (net (code "127") (name "unconnected-(U7-AUX_DA-Pad21)") (class "Default")
      (node (ref "U7") (pin "21") (pinfunction "AUX_DA_21") (pintype "bidirectional"))
    )
    (net (code "128") (name "unconnected-(U7-FSYNC-Pad11)") (class "Default")
      (node (ref "U7") (pin "11") (pinfunction "FSYNC_11") (pintype "bidirectional"))
    )
  )
)
